# 01_COREBOARD.net
KiCad netlist of a schematic drawn in Altium Designer
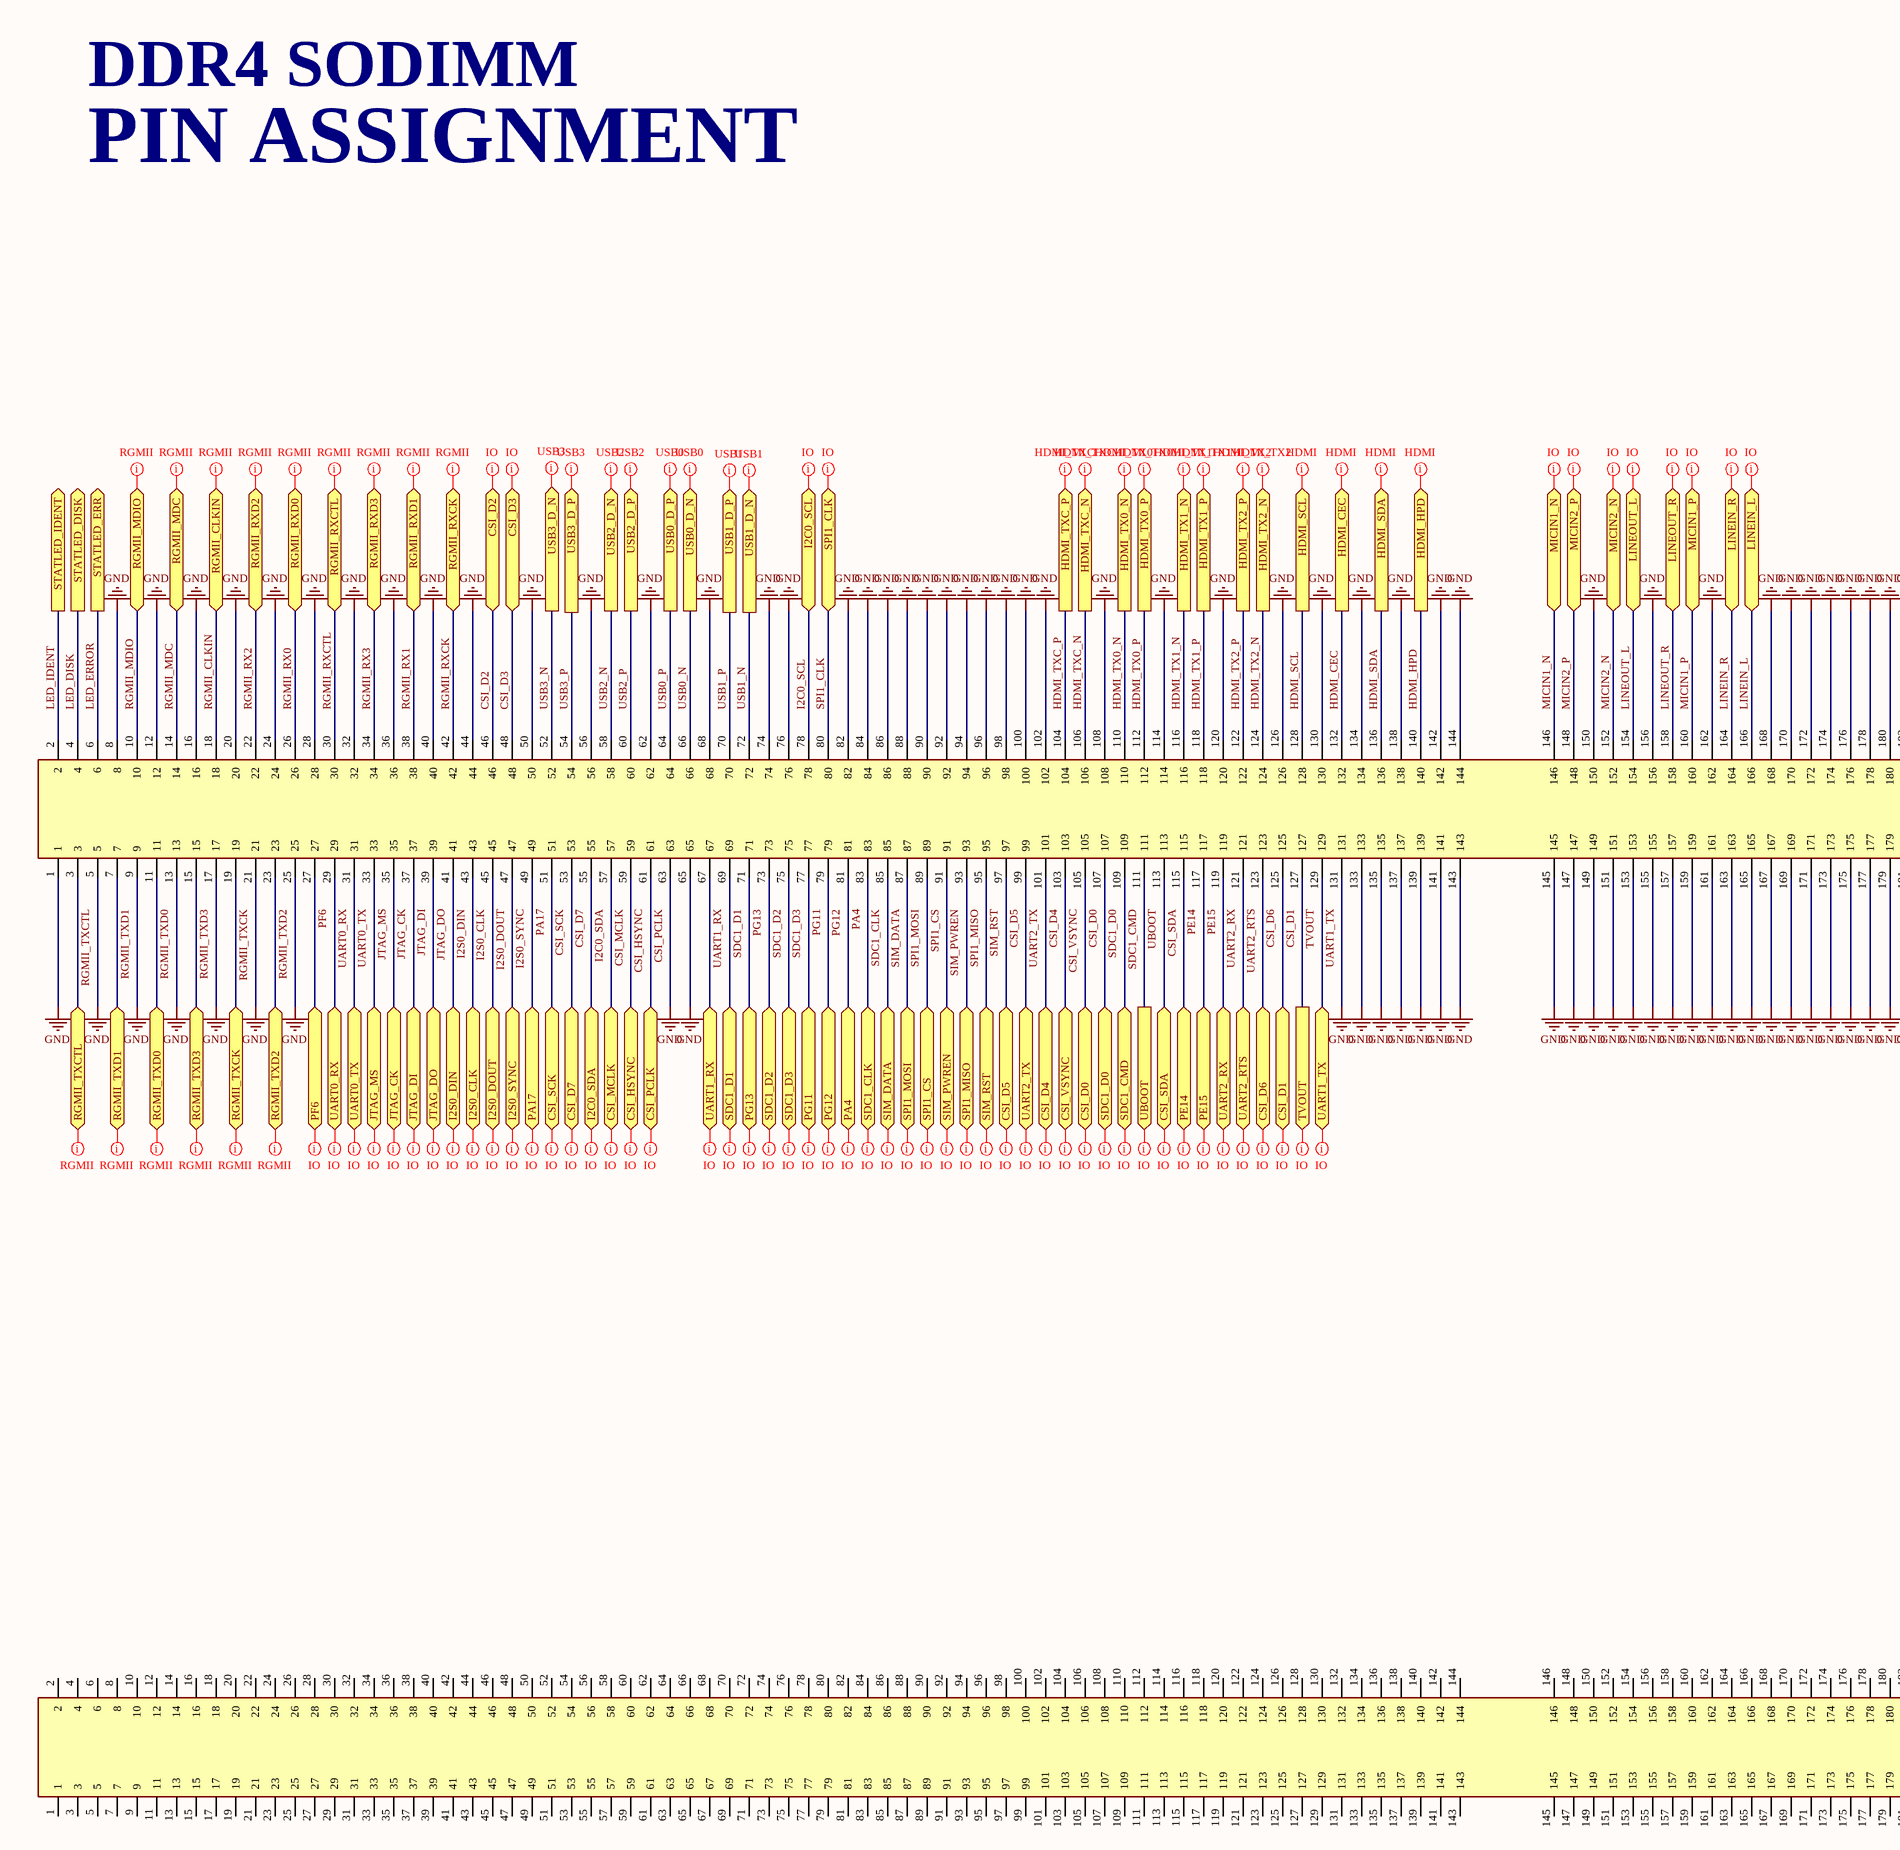
[diagram p0: 01_COREBOARD.SchDoc, left]
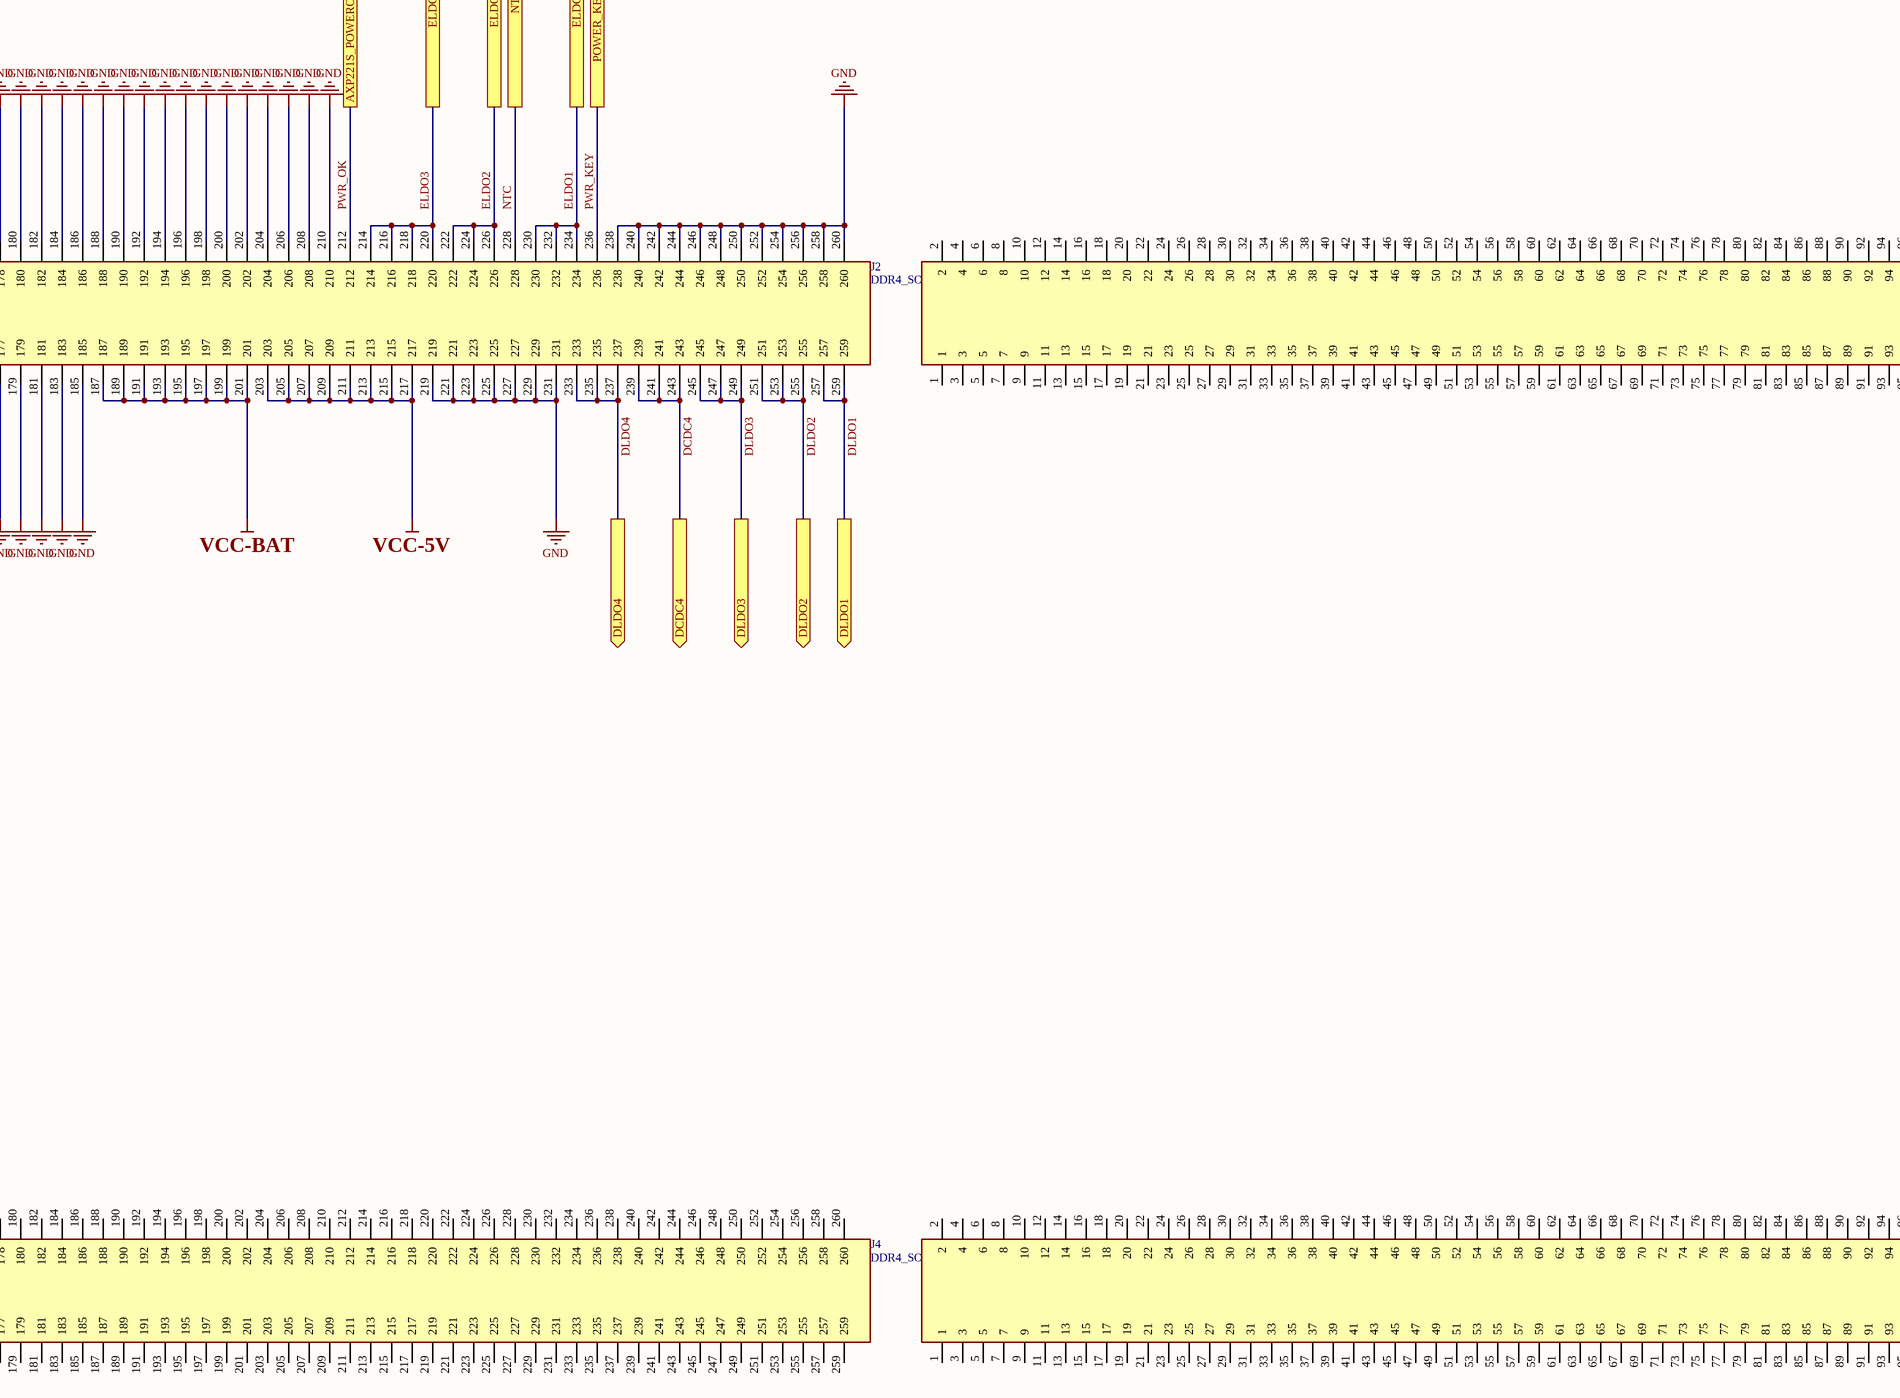
[diagram p1: 01_COREBOARD.SchDoc, middle]
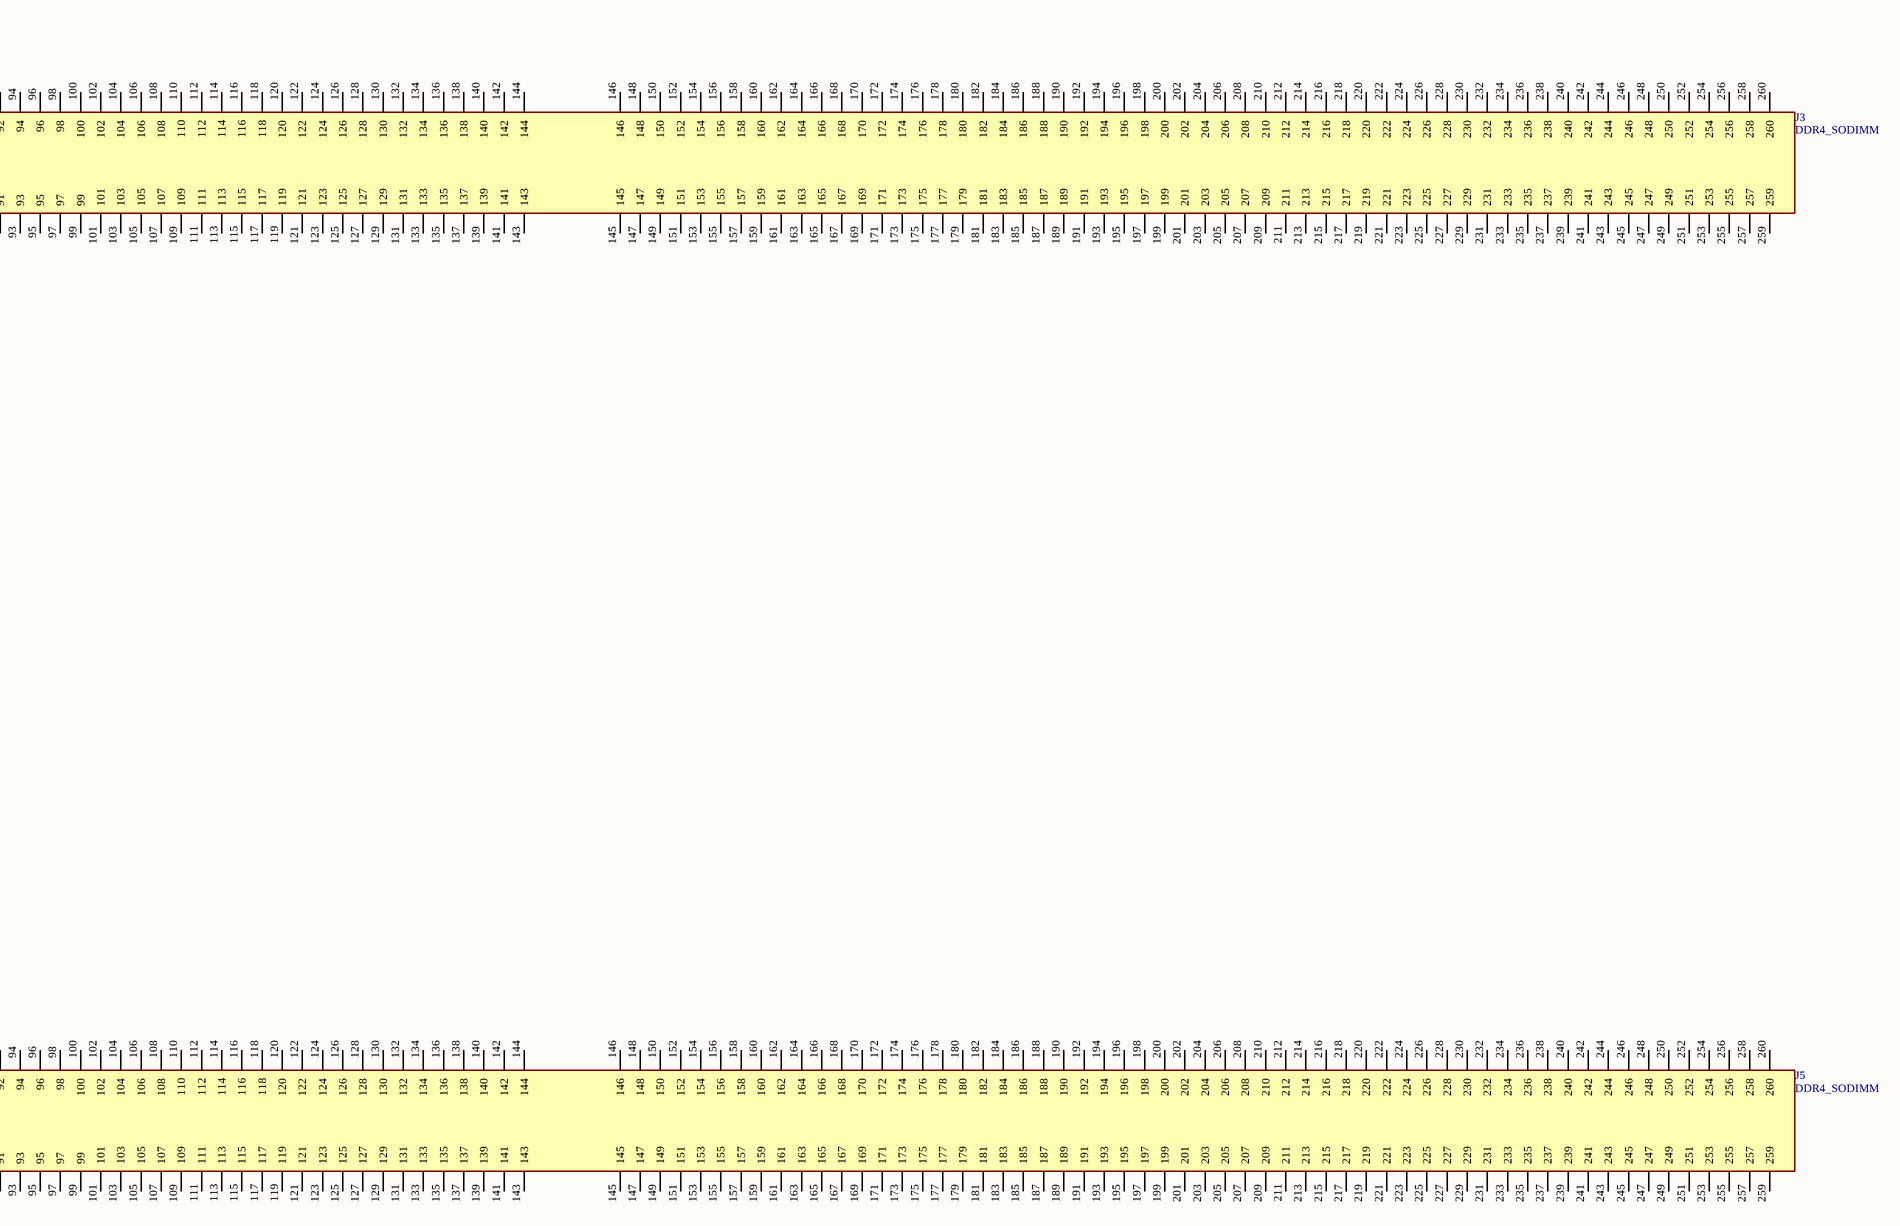
[diagram p2: 01_COREBOARD.SchDoc, right]

(export (version "E")
  (design (tool "Eeschema 10.0.6"))
  (components
    (comp (ref "J2")
      (value "DDR4_SODIMM")
      (footprint "DDR4_SODIMM")
      (libsource (lib "") (part "DDR4_SODIMM_1"))
    )
    (comp (ref "J3")
      (value "DDR4_SODIMM")
      (footprint "DDR4_SODIMM")
      (libsource (lib "MotherBoard") (part "DDR4_SODIMM"))
    )
    (comp (ref "J4")
      (value "DDR4_SODIMM")
      (footprint "DDR4_SODIMM")
      (libsource (lib "") (part "DDR4_SODIMM_1"))
    )
    (comp (ref "J5")
      (value "DDR4_SODIMM")
      (footprint "DDR4_SODIMM")
      (libsource (lib "MotherBoard") (part "DDR4_SODIMM"))
    )
  )
  (nets
    (net (code "1") (name "/CSI_D0") (class "Default")
      (node (ref "J2") (pin "105") (pinfunction "105_105") (pintype "passive"))
    )
    (net (code "2") (name "/CSI_D1") (class "Default")
      (node (ref "J2") (pin "125") (pinfunction "125_125") (pintype "passive"))
    )
    (net (code "3") (name "/CSI_D2") (class "Default")
      (node (ref "J2") (pin "46") (pinfunction "46_46") (pintype "passive"))
    )
    (net (code "4") (name "/CSI_D3") (class "Default")
      (node (ref "J2") (pin "48") (pinfunction "48_48") (pintype "passive"))
    )
    (net (code "5") (name "/CSI_D4") (class "Default")
      (node (ref "J2") (pin "101") (pinfunction "101_101") (pintype "passive"))
    )
    (net (code "6") (name "/CSI_D5") (class "Default")
      (node (ref "J2") (pin "97") (pinfunction "97_97") (pintype "passive"))
    )
    (net (code "7") (name "/CSI_D6") (class "Default")
      (node (ref "J2") (pin "123") (pinfunction "123_123") (pintype "passive"))
    )
    (net (code "8") (name "/CSI_D7") (class "Default")
      (node (ref "J2") (pin "53") (pinfunction "53_53") (pintype "passive"))
    )
    (net (code "9") (name "/CSI_HSYNC") (class "Default")
      (node (ref "J2") (pin "59") (pinfunction "59_59") (pintype "passive"))
    )
    (net (code "10") (name "/CSI_MCLK") (class "Default")
      (node (ref "J2") (pin "57") (pinfunction "57_57") (pintype "passive"))
    )
    (net (code "11") (name "/CSI_PCLK") (class "Default")
      (node (ref "J2") (pin "61") (pinfunction "61_61") (pintype "passive"))
    )
    (net (code "12") (name "/CSI_SCK") (class "Default")
      (node (ref "J2") (pin "51") (pinfunction "51_51") (pintype "passive"))
    )
    (net (code "13") (name "/CSI_SDA") (class "Default")
      (node (ref "J2") (pin "113") (pinfunction "113_113") (pintype "passive"))
    )
    (net (code "14") (name "/CSI_VSYNC") (class "Default")
      (node (ref "J2") (pin "103") (pinfunction "103_103") (pintype "passive"))
    )
    (net (code "15") (name "/DCDC4") (class "Default")
      (node (ref "J2") (pin "239") (pinfunction "239_239") (pintype "passive"))
      (node (ref "J2") (pin "241") (pinfunction "241_241") (pintype "passive"))
      (node (ref "J2") (pin "243") (pinfunction "243_243") (pintype "passive"))
    )
    (net (code "16") (name "/DLDO1") (class "Default")
      (node (ref "J2") (pin "257") (pinfunction "257_257") (pintype "passive"))
      (node (ref "J2") (pin "259") (pinfunction "259_259") (pintype "passive"))
    )
    (net (code "17") (name "/DLDO2") (class "Default")
      (node (ref "J2") (pin "251") (pinfunction "251_251") (pintype "passive"))
      (node (ref "J2") (pin "253") (pinfunction "253_253") (pintype "passive"))
      (node (ref "J2") (pin "255") (pinfunction "255_255") (pintype "passive"))
    )
    (net (code "18") (name "/DLDO3") (class "Default")
      (node (ref "J2") (pin "245") (pinfunction "245_245") (pintype "passive"))
      (node (ref "J2") (pin "247") (pinfunction "247_247") (pintype "passive"))
      (node (ref "J2") (pin "249") (pinfunction "249_249") (pintype "passive"))
    )
    (net (code "19") (name "/DLDO4") (class "Default")
      (node (ref "J2") (pin "233") (pinfunction "233_233") (pintype "passive"))
      (node (ref "J2") (pin "235") (pinfunction "235_235") (pintype "passive"))
      (node (ref "J2") (pin "237") (pinfunction "237_237") (pintype "passive"))
    )
    (net (code "20") (name "/ELDO1") (class "Default")
      (node (ref "J2") (pin "230") (pinfunction "230_230") (pintype "passive"))
      (node (ref "J2") (pin "232") (pinfunction "232_232") (pintype "passive"))
      (node (ref "J2") (pin "234") (pinfunction "234_234") (pintype "passive"))
    )
    (net (code "21") (name "/ELDO2") (class "Default")
      (node (ref "J2") (pin "222") (pinfunction "222_222") (pintype "passive"))
      (node (ref "J2") (pin "224") (pinfunction "224_224") (pintype "passive"))
      (node (ref "J2") (pin "226") (pinfunction "226_226") (pintype "passive"))
    )
    (net (code "22") (name "/ELDO3") (class "Default")
      (node (ref "J2") (pin "214") (pinfunction "214_214") (pintype "passive"))
      (node (ref "J2") (pin "216") (pinfunction "216_216") (pintype "passive"))
      (node (ref "J2") (pin "218") (pinfunction "218_218") (pintype "passive"))
      (node (ref "J2") (pin "220") (pinfunction "220_220") (pintype "passive"))
    )
    (net (code "23") (name "/HDMI_CEC") (class "Default")
      (node (ref "J2") (pin "132") (pinfunction "132_132") (pintype "passive"))
    )
    (net (code "24") (name "/HDMI_HPD") (class "Default")
      (node (ref "J2") (pin "140") (pinfunction "140_140") (pintype "passive"))
    )
    (net (code "25") (name "/HDMI_SCL") (class "Default")
      (node (ref "J2") (pin "128") (pinfunction "128_128") (pintype "passive"))
    )
    (net (code "26") (name "/HDMI_SDA") (class "Default")
      (node (ref "J2") (pin "136") (pinfunction "136_136") (pintype "passive"))
    )
    (net (code "27") (name "/HDMI_TX0_N") (class "Default")
      (node (ref "J2") (pin "110") (pinfunction "110_110") (pintype "passive"))
    )
    (net (code "28") (name "/HDMI_TX0_P") (class "Default")
      (node (ref "J2") (pin "112") (pinfunction "112_112") (pintype "passive"))
    )
    (net (code "29") (name "/HDMI_TX1_N") (class "Default")
      (node (ref "J2") (pin "116") (pinfunction "116_116") (pintype "passive"))
    )
    (net (code "30") (name "/HDMI_TX1_P") (class "Default")
      (node (ref "J2") (pin "118") (pinfunction "118_118") (pintype "passive"))
    )
    (net (code "31") (name "/HDMI_TX2_N") (class "Default")
      (node (ref "J2") (pin "124") (pinfunction "124_124") (pintype "passive"))
    )
    (net (code "32") (name "/HDMI_TX2_P") (class "Default")
      (node (ref "J2") (pin "122") (pinfunction "122_122") (pintype "passive"))
    )
    (net (code "33") (name "/HDMI_TXC_N") (class "Default")
      (node (ref "J2") (pin "106") (pinfunction "106_106") (pintype "passive"))
    )
    (net (code "34") (name "/HDMI_TXC_P") (class "Default")
      (node (ref "J2") (pin "104") (pinfunction "104_104") (pintype "passive"))
    )
    (net (code "35") (name "/I2C0_SCL") (class "Default")
      (node (ref "J2") (pin "78") (pinfunction "78_78") (pintype "passive"))
    )
    (net (code "36") (name "/I2C0_SDA") (class "Default")
      (node (ref "J2") (pin "55") (pinfunction "55_55") (pintype "passive"))
    )
    (net (code "37") (name "/I2S0_CLK") (class "Default")
      (node (ref "J2") (pin "43") (pinfunction "43_43") (pintype "passive"))
    )
    (net (code "38") (name "/I2S0_DIN") (class "Default")
      (node (ref "J2") (pin "41") (pinfunction "41_41") (pintype "passive"))
    )
    (net (code "39") (name "/I2S0_DOUT") (class "Default")
      (node (ref "J2") (pin "45") (pinfunction "45_45") (pintype "passive"))
    )
    (net (code "40") (name "/I2S0_SYNC") (class "Default")
      (node (ref "J2") (pin "47") (pinfunction "47_47") (pintype "passive"))
    )
    (net (code "41") (name "/JTAG_CK") (class "Default")
      (node (ref "J2") (pin "35") (pinfunction "35_35") (pintype "passive"))
    )
    (net (code "42") (name "/JTAG_DI") (class "Default")
      (node (ref "J2") (pin "37") (pinfunction "37_37") (pintype "passive"))
    )
    (net (code "43") (name "/JTAG_DO") (class "Default")
      (node (ref "J2") (pin "39") (pinfunction "39_39") (pintype "passive"))
    )
    (net (code "44") (name "/JTAG_MS") (class "Default")
      (node (ref "J2") (pin "33") (pinfunction "33_33") (pintype "passive"))
    )
    (net (code "45") (name "/LED_DISK") (class "Default")
      (node (ref "J2") (pin "4") (pinfunction "4_4") (pintype "passive"))
    )
    (net (code "46") (name "/LED_ERROR") (class "Default")
      (node (ref "J2") (pin "6") (pinfunction "6_6") (pintype "passive"))
    )
    (net (code "47") (name "/LED_IDENT") (class "Default")
      (node (ref "J2") (pin "2") (pinfunction "2_2") (pintype "passive"))
    )
    (net (code "48") (name "/LINEIN_L") (class "Default")
      (node (ref "J2") (pin "166") (pinfunction "166_166") (pintype "passive"))
    )
    (net (code "49") (name "/LINEIN_R") (class "Default")
      (node (ref "J2") (pin "164") (pinfunction "164_164") (pintype "passive"))
    )
    (net (code "50") (name "/LINEOUT_L") (class "Default")
      (node (ref "J2") (pin "154") (pinfunction "154_154") (pintype "passive"))
    )
    (net (code "51") (name "/LINEOUT_R") (class "Default")
      (node (ref "J2") (pin "158") (pinfunction "158_158") (pintype "passive"))
    )
    (net (code "52") (name "/MICIN1_N") (class "Default")
      (node (ref "J2") (pin "146") (pinfunction "146_146") (pintype "passive"))
    )
    (net (code "53") (name "/MICIN1_P") (class "Default")
      (node (ref "J2") (pin "160") (pinfunction "160_160") (pintype "passive"))
    )
    (net (code "54") (name "/MICIN2_N") (class "Default")
      (node (ref "J2") (pin "152") (pinfunction "152_152") (pintype "passive"))
    )
    (net (code "55") (name "/MICIN2_P") (class "Default")
      (node (ref "J2") (pin "148") (pinfunction "148_148") (pintype "passive"))
    )
    (net (code "56") (name "/NTC") (class "Default")
      (node (ref "J2") (pin "228") (pinfunction "228_228") (pintype "passive"))
    )
    (net (code "57") (name "/PA4") (class "Default")
      (node (ref "J2") (pin "81") (pinfunction "81_81") (pintype "passive"))
    )
    (net (code "58") (name "/PA17") (class "Default")
      (node (ref "J2") (pin "49") (pinfunction "49_49") (pintype "passive"))
    )
    (net (code "59") (name "/PE14") (class "Default")
      (node (ref "J2") (pin "115") (pinfunction "115_115") (pintype "passive"))
    )
    (net (code "60") (name "/PE15") (class "Default")
      (node (ref "J2") (pin "117") (pinfunction "117_117") (pintype "passive"))
    )
    (net (code "61") (name "/PF6") (class "Default")
      (node (ref "J2") (pin "27") (pinfunction "27_27") (pintype "passive"))
    )
    (net (code "62") (name "/PG11") (class "Default")
      (node (ref "J2") (pin "77") (pinfunction "77_77") (pintype "passive"))
    )
    (net (code "63") (name "/PG12") (class "Default")
      (node (ref "J2") (pin "79") (pinfunction "79_79") (pintype "passive"))
    )
    (net (code "64") (name "/PG13") (class "Default")
      (node (ref "J2") (pin "71") (pinfunction "71_71") (pintype "passive"))
    )
    (net (code "65") (name "/PWR_KEY") (class "Default")
      (node (ref "J2") (pin "236") (pinfunction "236_236") (pintype "passive"))
    )
    (net (code "66") (name "/PWR_OK") (class "Default")
      (node (ref "J2") (pin "212") (pinfunction "212_212") (pintype "passive"))
    )
    (net (code "67") (name "/RGMII_CLKIN") (class "Default")
      (node (ref "J2") (pin "18") (pinfunction "18_18") (pintype "passive"))
    )
    (net (code "68") (name "/RGMII_MDC") (class "Default")
      (node (ref "J2") (pin "14") (pinfunction "14_14") (pintype "passive"))
    )
    (net (code "69") (name "/RGMII_MDIO") (class "Default")
      (node (ref "J2") (pin "10") (pinfunction "10_10") (pintype "passive"))
    )
    (net (code "70") (name "/RGMII_RX0") (class "Default")
      (node (ref "J2") (pin "26") (pinfunction "26_26") (pintype "passive"))
    )
    (net (code "71") (name "/RGMII_RX1") (class "Default")
      (node (ref "J2") (pin "38") (pinfunction "38_38") (pintype "passive"))
    )
    (net (code "72") (name "/RGMII_RX2") (class "Default")
      (node (ref "J2") (pin "22") (pinfunction "22_22") (pintype "passive"))
    )
    (net (code "73") (name "/RGMII_RX3") (class "Default")
      (node (ref "J2") (pin "34") (pinfunction "34_34") (pintype "passive"))
    )
    (net (code "74") (name "/RGMII_RXCK") (class "Default")
      (node (ref "J2") (pin "42") (pinfunction "42_42") (pintype "passive"))
    )
    (net (code "75") (name "/RGMII_RXCTL") (class "Default")
      (node (ref "J2") (pin "30") (pinfunction "30_30") (pintype "passive"))
    )
    (net (code "76") (name "/RGMII_TXCK") (class "Default")
      (node (ref "J2") (pin "19") (pinfunction "19_19") (pintype "passive"))
    )
    (net (code "77") (name "/RGMII_TXCTL") (class "Default")
      (node (ref "J2") (pin "3") (pinfunction "3_3") (pintype "passive"))
    )
    (net (code "78") (name "/RGMII_TXD0") (class "Default")
      (node (ref "J2") (pin "11") (pinfunction "11_11") (pintype "passive"))
    )
    (net (code "79") (name "/RGMII_TXD1") (class "Default")
      (node (ref "J2") (pin "7") (pinfunction "7_7") (pintype "passive"))
    )
    (net (code "80") (name "/RGMII_TXD2") (class "Default")
      (node (ref "J2") (pin "23") (pinfunction "23_23") (pintype "passive"))
    )
    (net (code "81") (name "/RGMII_TXD3") (class "Default")
      (node (ref "J2") (pin "15") (pinfunction "15_15") (pintype "passive"))
    )
    (net (code "82") (name "/SDC1_CLK") (class "Default")
      (node (ref "J2") (pin "83") (pinfunction "83_83") (pintype "passive"))
    )
    (net (code "83") (name "/SDC1_CMD") (class "Default")
      (node (ref "J2") (pin "109") (pinfunction "109_109") (pintype "passive"))
    )
    (net (code "84") (name "/SDC1_D0") (class "Default")
      (node (ref "J2") (pin "107") (pinfunction "107_107") (pintype "passive"))
    )
    (net (code "85") (name "/SDC1_D1") (class "Default")
      (node (ref "J2") (pin "69") (pinfunction "69_69") (pintype "passive"))
    )
    (net (code "86") (name "/SDC1_D2") (class "Default")
      (node (ref "J2") (pin "73") (pinfunction "73_73") (pintype "passive"))
    )
    (net (code "87") (name "/SDC1_D3") (class "Default")
      (node (ref "J2") (pin "75") (pinfunction "75_75") (pintype "passive"))
    )
    (net (code "88") (name "/SIM_DATA") (class "Default")
      (node (ref "J2") (pin "85") (pinfunction "85_85") (pintype "passive"))
    )
    (net (code "89") (name "/SIM_PWREN") (class "Default")
      (node (ref "J2") (pin "91") (pinfunction "91_91") (pintype "passive"))
    )
    (net (code "90") (name "/SIM_RST") (class "Default")
      (node (ref "J2") (pin "95") (pinfunction "95_95") (pintype "passive"))
    )
    (net (code "91") (name "/SPI1_CLK") (class "Default")
      (node (ref "J2") (pin "80") (pinfunction "80_80") (pintype "passive"))
    )
    (net (code "92") (name "/SPI1_CS") (class "Default")
      (node (ref "J2") (pin "89") (pinfunction "89_89") (pintype "passive"))
    )
    (net (code "93") (name "/SPI1_MISO") (class "Default")
      (node (ref "J2") (pin "93") (pinfunction "93_93") (pintype "passive"))
    )
    (net (code "94") (name "/SPI1_MOSI") (class "Default")
      (node (ref "J2") (pin "87") (pinfunction "87_87") (pintype "passive"))
    )
    (net (code "95") (name "/TVOUT") (class "Default")
      (node (ref "J2") (pin "127") (pinfunction "127_127") (pintype "passive"))
    )
    (net (code "96") (name "/UART0_RX") (class "Default")
      (node (ref "J2") (pin "29") (pinfunction "29_29") (pintype "passive"))
    )
    (net (code "97") (name "/UART0_TX") (class "Default")
      (node (ref "J2") (pin "31") (pinfunction "31_31") (pintype "passive"))
    )
    (net (code "98") (name "/UART1_RX") (class "Default")
      (node (ref "J2") (pin "67") (pinfunction "67_67") (pintype "passive"))
    )
    (net (code "99") (name "/UART1_TX") (class "Default")
      (node (ref "J2") (pin "129") (pinfunction "129_129") (pintype "passive"))
    )
    (net (code "100") (name "/UART2_RTS") (class "Default")
      (node (ref "J2") (pin "121") (pinfunction "121_121") (pintype "passive"))
    )
    (net (code "101") (name "/UART2_RX") (class "Default")
      (node (ref "J2") (pin "119") (pinfunction "119_119") (pintype "passive"))
    )
    (net (code "102") (name "/UART2_TX") (class "Default")
      (node (ref "J2") (pin "99") (pinfunction "99_99") (pintype "passive"))
    )
    (net (code "103") (name "/UBOOT") (class "Default")
      (node (ref "J2") (pin "111") (pinfunction "111_111") (pintype "passive"))
    )
    (net (code "104") (name "/USB0_N") (class "Default")
      (node (ref "J2") (pin "66") (pinfunction "66_66") (pintype "passive"))
    )
    (net (code "105") (name "/USB0_P") (class "Default")
      (node (ref "J2") (pin "64") (pinfunction "64_64") (pintype "passive"))
    )
    (net (code "106") (name "/USB1_N") (class "Default")
      (node (ref "J2") (pin "72") (pinfunction "72_72") (pintype "passive"))
    )
    (net (code "107") (name "/USB1_P") (class "Default")
      (node (ref "J2") (pin "70") (pinfunction "70_70") (pintype "passive"))
    )
    (net (code "108") (name "/USB2_N") (class "Default")
      (node (ref "J2") (pin "58") (pinfunction "58_58") (pintype "passive"))
    )
    (net (code "109") (name "/USB2_P") (class "Default")
      (node (ref "J2") (pin "60") (pinfunction "60_60") (pintype "passive"))
    )
    (net (code "110") (name "/USB3_N") (class "Default")
      (node (ref "J2") (pin "52") (pinfunction "52_52") (pintype "passive"))
    )
    (net (code "111") (name "/USB3_P") (class "Default")
      (node (ref "J2") (pin "54") (pinfunction "54_54") (pintype "passive"))
    )
    (net (code "112") (name "GND") (class "Default")
      (node (ref "J2") (pin "1") (pinfunction "1_1") (pintype "passive"))
      (node (ref "J2") (pin "100") (pinfunction "100_100") (pintype "passive"))
      (node (ref "J2") (pin "102") (pinfunction "102_102") (pintype "passive"))
      (node (ref "J2") (pin "108") (pinfunction "108_108") (pintype "passive"))
      (node (ref "J2") (pin "114") (pinfunction "114_114") (pintype "passive"))
      (node (ref "J2") (pin "12") (pinfunction "12_12") (pintype "passive"))
      (node (ref "J2") (pin "120") (pinfunction "120_120") (pintype "passive"))
      (node (ref "J2") (pin "126") (pinfunction "126_126") (pintype "passive"))
      (node (ref "J2") (pin "13") (pinfunction "13_13") (pintype "passive"))
      (node (ref "J2") (pin "130") (pinfunction "130_130") (pintype "passive"))
      (node (ref "J2") (pin "131") (pinfunction "131_131") (pintype "passive"))
      (node (ref "J2") (pin "133") (pinfunction "133_133") (pintype "passive"))
      (node (ref "J2") (pin "134") (pinfunction "134_134") (pintype "passive"))
      (node (ref "J2") (pin "135") (pinfunction "135_135") (pintype "passive"))
      (node (ref "J2") (pin "137") (pinfunction "137_137") (pintype "passive"))
      (node (ref "J2") (pin "138") (pinfunction "138_138") (pintype "passive"))
      (node (ref "J2") (pin "139") (pinfunction "139_139") (pintype "passive"))
      (node (ref "J2") (pin "141") (pinfunction "141_141") (pintype "passive"))
      (node (ref "J2") (pin "142") (pinfunction "142_142") (pintype "passive"))
      (node (ref "J2") (pin "143") (pinfunction "143_143") (pintype "passive"))
      (node (ref "J2") (pin "144") (pinfunction "144_144") (pintype "passive"))
      (node (ref "J2") (pin "145") (pinfunction "145_145") (pintype "passive"))
      (node (ref "J2") (pin "147") (pinfunction "147_147") (pintype "passive"))
      (node (ref "J2") (pin "149") (pinfunction "149_149") (pintype "passive"))
      (node (ref "J2") (pin "150") (pinfunction "150_150") (pintype "passive"))
      (node (ref "J2") (pin "151") (pinfunction "151_151") (pintype "passive"))
      (node (ref "J2") (pin "153") (pinfunction "153_153") (pintype "passive"))
      (node (ref "J2") (pin "155") (pinfunction "155_155") (pintype "passive"))
      (node (ref "J2") (pin "156") (pinfunction "156_156") (pintype "passive"))
      (node (ref "J2") (pin "157") (pinfunction "157_157") (pintype "passive"))
      (node (ref "J2") (pin "159") (pinfunction "159_159") (pintype "passive"))
      (node (ref "J2") (pin "16") (pinfunction "16_16") (pintype "passive"))
      (node (ref "J2") (pin "161") (pinfunction "161_161") (pintype "passive"))
      (node (ref "J2") (pin "162") (pinfunction "162_162") (pintype "passive"))
      (node (ref "J2") (pin "163") (pinfunction "163_163") (pintype "passive"))
      (node (ref "J2") (pin "165") (pinfunction "165_165") (pintype "passive"))
      (node (ref "J2") (pin "167") (pinfunction "167_167") (pintype "passive"))
      (node (ref "J2") (pin "168") (pinfunction "168_168") (pintype "passive"))
      (node (ref "J2") (pin "169") (pinfunction "169_169") (pintype "passive"))
      (node (ref "J2") (pin "17") (pinfunction "17_17") (pintype "passive"))
      (node (ref "J2") (pin "170") (pinfunction "170_170") (pintype "passive"))
      (node (ref "J2") (pin "171") (pinfunction "171_171") (pintype "passive"))
      (node (ref "J2") (pin "172") (pinfunction "172_172") (pintype "passive"))
      (node (ref "J2") (pin "173") (pinfunction "173_173") (pintype "passive"))
      (node (ref "J2") (pin "174") (pinfunction "174_174") (pintype "passive"))
      (node (ref "J2") (pin "175") (pinfunction "175_175") (pintype "passive"))
      (node (ref "J2") (pin "176") (pinfunction "176_176") (pintype "passive"))
      (node (ref "J2") (pin "177") (pinfunction "177_177") (pintype "passive"))
      (node (ref "J2") (pin "178") (pinfunction "178_178") (pintype "passive"))
      (node (ref "J2") (pin "179") (pinfunction "179_179") (pintype "passive"))
      (node (ref "J2") (pin "180") (pinfunction "180_180") (pintype "passive"))
      (node (ref "J2") (pin "181") (pinfunction "181_181") (pintype "passive"))
      (node (ref "J2") (pin "182") (pinfunction "182_182") (pintype "passive"))
      (node (ref "J2") (pin "183") (pinfunction "183_183") (pintype "passive"))
      (node (ref "J2") (pin "184") (pinfunction "184_184") (pintype "passive"))
      (node (ref "J2") (pin "185") (pinfunction "185_185") (pintype "passive"))
      (node (ref "J2") (pin "186") (pinfunction "186_186") (pintype "passive"))
      (node (ref "J2") (pin "188") (pinfunction "188_188") (pintype "passive"))
      (node (ref "J2") (pin "190") (pinfunction "190_190") (pintype "passive"))
      (node (ref "J2") (pin "192") (pinfunction "192_192") (pintype "passive"))
      (node (ref "J2") (pin "194") (pinfunction "194_194") (pintype "passive"))
      (node (ref "J2") (pin "196") (pinfunction "196_196") (pintype "passive"))
      (node (ref "J2") (pin "198") (pinfunction "198_198") (pintype "passive"))
      (node (ref "J2") (pin "20") (pinfunction "20_20") (pintype "passive"))
      (node (ref "J2") (pin "200") (pinfunction "200_200") (pintype "passive"))
      (node (ref "J2") (pin "202") (pinfunction "202_202") (pintype "passive"))
      (node (ref "J2") (pin "204") (pinfunction "204_204") (pintype "passive"))
      (node (ref "J2") (pin "206") (pinfunction "206_206") (pintype "passive"))
      (node (ref "J2") (pin "208") (pinfunction "208_208") (pintype "passive"))
      (node (ref "J2") (pin "21") (pinfunction "21_21") (pintype "passive"))
      (node (ref "J2") (pin "210") (pinfunction "210_210") (pintype "passive"))
      (node (ref "J2") (pin "219") (pinfunction "219_219") (pintype "passive"))
      (node (ref "J2") (pin "221") (pinfunction "221_221") (pintype "passive"))
      (node (ref "J2") (pin "223") (pinfunction "223_223") (pintype "passive"))
      (node (ref "J2") (pin "225") (pinfunction "225_225") (pintype "passive"))
      (node (ref "J2") (pin "227") (pinfunction "227_227") (pintype "passive"))
      (node (ref "J2") (pin "229") (pinfunction "229_229") (pintype "passive"))
      (node (ref "J2") (pin "231") (pinfunction "231_231") (pintype "passive"))
      (node (ref "J2") (pin "238") (pinfunction "238_238") (pintype "passive"))
      (node (ref "J2") (pin "24") (pinfunction "24_24") (pintype "passive"))
      (node (ref "J2") (pin "240") (pinfunction "240_240") (pintype "passive"))
      (node (ref "J2") (pin "242") (pinfunction "242_242") (pintype "passive"))
      (node (ref "J2") (pin "244") (pinfunction "244_244") (pintype "passive"))
      (node (ref "J2") (pin "246") (pinfunction "246_246") (pintype "passive"))
      (node (ref "J2") (pin "248") (pinfunction "248_248") (pintype "passive"))
      (node (ref "J2") (pin "25") (pinfunction "25_25") (pintype "passive"))
      (node (ref "J2") (pin "250") (pinfunction "250_250") (pintype "passive"))
      (node (ref "J2") (pin "252") (pinfunction "252_252") (pintype "passive"))
      (node (ref "J2") (pin "254") (pinfunction "254_254") (pintype "passive"))
      (node (ref "J2") (pin "256") (pinfunction "256_256") (pintype "passive"))
      (node (ref "J2") (pin "258") (pinfunction "258_258") (pintype "passive"))
      (node (ref "J2") (pin "260") (pinfunction "260_260") (pintype "passive"))
      (node (ref "J2") (pin "28") (pinfunction "28_28") (pintype "passive"))
      (node (ref "J2") (pin "32") (pinfunction "32_32") (pintype "passive"))
      (node (ref "J2") (pin "36") (pinfunction "36_36") (pintype "passive"))
      (node (ref "J2") (pin "40") (pinfunction "40_40") (pintype "passive"))
      (node (ref "J2") (pin "44") (pinfunction "44_44") (pintype "passive"))
      (node (ref "J2") (pin "5") (pinfunction "5_5") (pintype "passive"))
      (node (ref "J2") (pin "50") (pinfunction "50_50") (pintype "passive"))
      (node (ref "J2") (pin "56") (pinfunction "56_56") (pintype "passive"))
      (node (ref "J2") (pin "62") (pinfunction "62_62") (pintype "passive"))
      (node (ref "J2") (pin "63") (pinfunction "63_63") (pintype "passive"))
      (node (ref "J2") (pin "65") (pinfunction "65_65") (pintype "passive"))
      (node (ref "J2") (pin "68") (pinfunction "68_68") (pintype "passive"))
      (node (ref "J2") (pin "74") (pinfunction "74_74") (pintype "passive"))
      (node (ref "J2") (pin "76") (pinfunction "76_76") (pintype "passive"))
      (node (ref "J2") (pin "8") (pinfunction "8_8") (pintype "passive"))
      (node (ref "J2") (pin "82") (pinfunction "82_82") (pintype "passive"))
      (node (ref "J2") (pin "84") (pinfunction "84_84") (pintype "passive"))
      (node (ref "J2") (pin "86") (pinfunction "86_86") (pintype "passive"))
      (node (ref "J2") (pin "88") (pinfunction "88_88") (pintype "passive"))
      (node (ref "J2") (pin "9") (pinfunction "9_9") (pintype "passive"))
      (node (ref "J2") (pin "90") (pinfunction "90_90") (pintype "passive"))
      (node (ref "J2") (pin "92") (pinfunction "92_92") (pintype "passive"))
      (node (ref "J2") (pin "94") (pinfunction "94_94") (pintype "passive"))
      (node (ref "J2") (pin "96") (pinfunction "96_96") (pintype "passive"))
      (node (ref "J2") (pin "98") (pinfunction "98_98") (pintype "passive"))
    )
    (net (code "113") (name "VCC-5V") (class "Default")
      (node (ref "J2") (pin "203") (pinfunction "203_203") (pintype "passive"))
      (node (ref "J2") (pin "205") (pinfunction "205_205") (pintype "passive"))
      (node (ref "J2") (pin "207") (pinfunction "207_207") (pintype "passive"))
      (node (ref "J2") (pin "209") (pinfunction "209_209") (pintype "passive"))
      (node (ref "J2") (pin "211") (pinfunction "211_211") (pintype "passive"))
      (node (ref "J2") (pin "213") (pinfunction "213_213") (pintype "passive"))
      (node (ref "J2") (pin "215") (pinfunction "215_215") (pintype "passive"))
      (node (ref "J2") (pin "217") (pinfunction "217_217") (pintype "passive"))
    )
    (net (code "114") (name "VCC-BAT") (class "Default")
      (node (ref "J2") (pin "187") (pinfunction "187_187") (pintype "passive"))
      (node (ref "J2") (pin "189") (pinfunction "189_189") (pintype "passive"))
      (node (ref "J2") (pin "191") (pinfunction "191_191") (pintype "passive"))
      (node (ref "J2") (pin "193") (pinfunction "193_193") (pintype "passive"))
      (node (ref "J2") (pin "195") (pinfunction "195_195") (pintype "passive"))
      (node (ref "J2") (pin "197") (pinfunction "197_197") (pintype "passive"))
      (node (ref "J2") (pin "199") (pinfunction "199_199") (pintype "passive"))
      (node (ref "J2") (pin "201") (pinfunction "201_201") (pintype "passive"))
    )
    (net (code "115") (name "unconnected-(J3-Pad1)") (class "Default")
      (node (ref "J3") (pin "1") (pinfunction "1_1") (pintype "passive"))
    )
    (net (code "116") (name "unconnected-(J3-Pad2)") (class "Default")
      (node (ref "J3") (pin "2") (pinfunction "2_2") (pintype "passive"))
    )
    (net (code "117") (name "unconnected-(J3-Pad3)") (class "Default")
      (node (ref "J3") (pin "3") (pinfunction "3_3") (pintype "passive"))
    )
    (net (code "118") (name "unconnected-(J3-Pad4)") (class "Default")
      (node (ref "J3") (pin "4") (pinfunction "4_4") (pintype "passive"))
    )
    (net (code "119") (name "unconnected-(J3-Pad5)") (class "Default")
      (node (ref "J3") (pin "5") (pinfunction "5_5") (pintype "passive"))
    )
    (net (code "120") (name "unconnected-(J3-Pad6)") (class "Default")
      (node (ref "J3") (pin "6") (pinfunction "6_6") (pintype "passive"))
    )
    (net (code "121") (name "unconnected-(J3-Pad7)") (class "Default")
      (node (ref "J3") (pin "7") (pinfunction "7_7") (pintype "passive"))
    )
    (net (code "122") (name "unconnected-(J3-Pad8)") (class "Default")
      (node (ref "J3") (pin "8") (pinfunction "8_8") (pintype "passive"))
    )
    (net (code "123") (name "unconnected-(J3-Pad9)") (class "Default")
      (node (ref "J3") (pin "9") (pinfunction "9_9") (pintype "passive"))
    )
    (net (code "124") (name "unconnected-(J3-Pad10)") (class "Default")
      (node (ref "J3") (pin "10") (pinfunction "10_10") (pintype "passive"))
    )
    (net (code "125") (name "unconnected-(J3-Pad11)") (class "Default")
      (node (ref "J3") (pin "11") (pinfunction "11_11") (pintype "passive"))
    )
    (net (code "126") (name "unconnected-(J3-Pad12)") (class "Default")
      (node (ref "J3") (pin "12") (pinfunction "12_12") (pintype "passive"))
    )
    (net (code "127") (name "unconnected-(J3-Pad13)") (class "Default")
      (node (ref "J3") (pin "13") (pinfunction "13_13") (pintype "passive"))
    )
    (net (code "128") (name "unconnected-(J3-Pad14)") (class "Default")
      (node (ref "J3") (pin "14") (pinfunction "14_14") (pintype "passive"))
    )
    (net (code "129") (name "unconnected-(J3-Pad15)") (class "Default")
      (node (ref "J3") (pin "15") (pinfunction "15_15") (pintype "passive"))
    )
    (net (code "130") (name "unconnected-(J3-Pad16)") (class "Default")
      (node (ref "J3") (pin "16") (pinfunction "16_16") (pintype "passive"))
    )
    (net (code "131") (name "unconnected-(J3-Pad17)") (class "Default")
      (node (ref "J3") (pin "17") (pinfunction "17_17") (pintype "passive"))
    )
    (net (code "132") (name "unconnected-(J3-Pad18)") (class "Default")
      (node (ref "J3") (pin "18") (pinfunction "18_18") (pintype "passive"))
    )
    (net (code "133") (name "unconnected-(J3-Pad19)") (class "Default")
      (node (ref "J3") (pin "19") (pinfunction "19_19") (pintype "passive"))
    )
    (net (code "134") (name "unconnected-(J3-Pad20)") (class "Default")
      (node (ref "J3") (pin "20") (pinfunction "20_20") (pintype "passive"))
    )
    (net (code "135") (name "unconnected-(J3-Pad21)") (class "Default")
      (node (ref "J3") (pin "21") (pinfunction "21_21") (pintype "passive"))
    )
    (net (code "136") (name "unconnected-(J3-Pad22)") (class "Default")
      (node (ref "J3") (pin "22") (pinfunction "22_22") (pintype "passive"))
    )
    (net (code "137") (name "unconnected-(J3-Pad23)") (class "Default")
      (node (ref "J3") (pin "23") (pinfunction "23_23") (pintype "passive"))
    )
    (net (code "138") (name "unconnected-(J3-Pad24)") (class "Default")
      (node (ref "J3") (pin "24") (pinfunction "24_24") (pintype "passive"))
    )
    (net (code "139") (name "unconnected-(J3-Pad25)") (class "Default")
      (node (ref "J3") (pin "25") (pinfunction "25_25") (pintype "passive"))
    )
    (net (code "140") (name "unconnected-(J3-Pad26)") (class "Default")
      (node (ref "J3") (pin "26") (pinfunction "26_26") (pintype "passive"))
    )
    (net (code "141") (name "unconnected-(J3-Pad27)") (class "Default")
      (node (ref "J3") (pin "27") (pinfunction "27_27") (pintype "passive"))
    )
    (net (code "142") (name "unconnected-(J3-Pad28)") (class "Default")
      (node (ref "J3") (pin "28") (pinfunction "28_28") (pintype "passive"))
    )
    (net (code "143") (name "unconnected-(J3-Pad29)") (class "Default")
      (node (ref "J3") (pin "29") (pinfunction "29_29") (pintype "passive"))
    )
    (net (code "144") (name "unconnected-(J3-Pad30)") (class "Default")
      (node (ref "J3") (pin "30") (pinfunction "30_30") (pintype "passive"))
    )
    (net (code "145") (name "unconnected-(J3-Pad31)") (class "Default")
      (node (ref "J3") (pin "31") (pinfunction "31_31") (pintype "passive"))
    )
    (net (code "146") (name "unconnected-(J3-Pad32)") (class "Default")
      (node (ref "J3") (pin "32") (pinfunction "32_32") (pintype "passive"))
    )
    (net (code "147") (name "unconnected-(J3-Pad33)") (class "Default")
      (node (ref "J3") (pin "33") (pinfunction "33_33") (pintype "passive"))
    )
    (net (code "148") (name "unconnected-(J3-Pad34)") (class "Default")
      (node (ref "J3") (pin "34") (pinfunction "34_34") (pintype "passive"))
    )
    (net (code "149") (name "unconnected-(J3-Pad35)") (class "Default")
      (node (ref "J3") (pin "35") (pinfunction "35_35") (pintype "passive"))
    )
    (net (code "150") (name "unconnected-(J3-Pad36)") (class "Default")
      (node (ref "J3") (pin "36") (pinfunction "36_36") (pintype "passive"))
    )
    (net (code "151") (name "unconnected-(J3-Pad37)") (class "Default")
      (node (ref "J3") (pin "37") (pinfunction "37_37") (pintype "passive"))
    )
    (net (code "152") (name "unconnected-(J3-Pad38)") (class "Default")
      (node (ref "J3") (pin "38") (pinfunction "38_38") (pintype "passive"))
    )
    (net (code "153") (name "unconnected-(J3-Pad39)") (class "Default")
      (node (ref "J3") (pin "39") (pinfunction "39_39") (pintype "passive"))
    )
    (net (code "154") (name "unconnected-(J3-Pad40)") (class "Default")
      (node (ref "J3") (pin "40") (pinfunction "40_40") (pintype "passive"))
    )
    (net (code "155") (name "unconnected-(J3-Pad41)") (class "Default")
      (node (ref "J3") (pin "41") (pinfunction "41_41") (pintype "passive"))
    )
    (net (code "156") (name "unconnected-(J3-Pad42)") (class "Default")
      (node (ref "J3") (pin "42") (pinfunction "42_42") (pintype "passive"))
    )
    (net (code "157") (name "unconnected-(J3-Pad43)") (class "Default")
      (node (ref "J3") (pin "43") (pinfunction "43_43") (pintype "passive"))
    )
    (net (code "158") (name "unconnected-(J3-Pad44)") (class "Default")
      (node (ref "J3") (pin "44") (pinfunction "44_44") (pintype "passive"))
    )
    (net (code "159") (name "unconnected-(J3-Pad45)") (class "Default")
      (node (ref "J3") (pin "45") (pinfunction "45_45") (pintype "passive"))
    )
    (net (code "160") (name "unconnected-(J3-Pad46)") (class "Default")
      (node (ref "J3") (pin "46") (pinfunction "46_46") (pintype "passive"))
    )
    (net (code "161") (name "unconnected-(J3-Pad47)") (class "Default")
      (node (ref "J3") (pin "47") (pinfunction "47_47") (pintype "passive"))
    )
    (net (code "162") (name "unconnected-(J3-Pad48)") (class "Default")
      (node (ref "J3") (pin "48") (pinfunction "48_48") (pintype "passive"))
    )
    (net (code "163") (name "unconnected-(J3-Pad49)") (class "Default")
      (node (ref "J3") (pin "49") (pinfunction "49_49") (pintype "passive"))
    )
    (net (code "164") (name "unconnected-(J3-Pad50)") (class "Default")
      (node (ref "J3") (pin "50") (pinfunction "50_50") (pintype "passive"))
    )
    (net (code "165") (name "unconnected-(J3-Pad51)") (class "Default")
      (node (ref "J3") (pin "51") (pinfunction "51_51") (pintype "passive"))
    )
    (net (code "166") (name "unconnected-(J3-Pad52)") (class "Default")
      (node (ref "J3") (pin "52") (pinfunction "52_52") (pintype "passive"))
    )
    (net (code "167") (name "unconnected-(J3-Pad53)") (class "Default")
      (node (ref "J3") (pin "53") (pinfunction "53_53") (pintype "passive"))
    )
    (net (code "168") (name "unconnected-(J3-Pad54)") (class "Default")
      (node (ref "J3") (pin "54") (pinfunction "54_54") (pintype "passive"))
    )
    (net (code "169") (name "unconnected-(J3-Pad55)") (class "Default")
      (node (ref "J3") (pin "55") (pinfunction "55_55") (pintype "passive"))
    )
    (net (code "170") (name "unconnected-(J3-Pad56)") (class "Default")
      (node (ref "J3") (pin "56") (pinfunction "56_56") (pintype "passive"))
    )
    (net (code "171") (name "unconnected-(J3-Pad57)") (class "Default")
      (node (ref "J3") (pin "57") (pinfunction "57_57") (pintype "passive"))
    )
    (net (code "172") (name "unconnected-(J3-Pad58)") (class "Default")
      (node (ref "J3") (pin "58") (pinfunction "58_58") (pintype "passive"))
    )
    (net (code "173") (name "unconnected-(J3-Pad59)") (class "Default")
      (node (ref "J3") (pin "59") (pinfunction "59_59") (pintype "passive"))
    )
    (net (code "174") (name "unconnected-(J3-Pad60)") (class "Default")
      (node (ref "J3") (pin "60") (pinfunction "60_60") (pintype "passive"))
    )
    (net (code "175") (name "unconnected-(J3-Pad61)") (class "Default")
      (node (ref "J3") (pin "61") (pinfunction "61_61") (pintype "passive"))
    )
    (net (code "176") (name "unconnected-(J3-Pad62)") (class "Default")
      (node (ref "J3") (pin "62") (pinfunction "62_62") (pintype "passive"))
    )
    (net (code "177") (name "unconnected-(J3-Pad63)") (class "Default")
      (node (ref "J3") (pin "63") (pinfunction "63_63") (pintype "passive"))
    )
    (net (code "178") (name "unconnected-(J3-Pad64)") (class "Default")
      (node (ref "J3") (pin "64") (pinfunction "64_64") (pintype "passive"))
    )
    (net (code "179") (name "unconnected-(J3-Pad65)") (class "Default")
      (node (ref "J3") (pin "65") (pinfunction "65_65") (pintype "passive"))
    )
    (net (code "180") (name "unconnected-(J3-Pad66)") (class "Default")
      (node (ref "J3") (pin "66") (pinfunction "66_66") (pintype "passive"))
    )
    (net (code "181") (name "unconnected-(J3-Pad67)") (class "Default")
      (node (ref "J3") (pin "67") (pinfunction "67_67") (pintype "passive"))
    )
    (net (code "182") (name "unconnected-(J3-Pad68)") (class "Default")
      (node (ref "J3") (pin "68") (pinfunction "68_68") (pintype "passive"))
    )
    (net (code "183") (name "unconnected-(J3-Pad69)") (class "Default")
      (node (ref "J3") (pin "69") (pinfunction "69_69") (pintype "passive"))
    )
    (net (code "184") (name "unconnected-(J3-Pad70)") (class "Default")
      (node (ref "J3") (pin "70") (pinfunction "70_70") (pintype "passive"))
    )
    (net (code "185") (name "unconnected-(J3-Pad71)") (class "Default")
      (node (ref "J3") (pin "71") (pinfunction "71_71") (pintype "passive"))
    )
    (net (code "186") (name "unconnected-(J3-Pad72)") (class "Default")
      (node (ref "J3") (pin "72") (pinfunction "72_72") (pintype "passive"))
    )
    (net (code "187") (name "unconnected-(J3-Pad73)") (class "Default")
      (node (ref "J3") (pin "73") (pinfunction "73_73") (pintype "passive"))
    )
    (net (code "188") (name "unconnected-(J3-Pad74)") (class "Default")
      (node (ref "J3") (pin "74") (pinfunction "74_74") (pintype "passive"))
    )
    (net (code "189") (name "unconnected-(J3-Pad75)") (class "Default")
      (node (ref "J3") (pin "75") (pinfunction "75_75") (pintype "passive"))
    )
    (net (code "190") (name "unconnected-(J3-Pad76)") (class "Default")
      (node (ref "J3") (pin "76") (pinfunction "76_76") (pintype "passive"))
    )
    (net (code "191") (name "unconnected-(J3-Pad77)") (class "Default")
      (node (ref "J3") (pin "77") (pinfunction "77_77") (pintype "passive"))
    )
    (net (code "192") (name "unconnected-(J3-Pad78)") (class "Default")
      (node (ref "J3") (pin "78") (pinfunction "78_78") (pintype "passive"))
    )
    (net (code "193") (name "unconnected-(J3-Pad79)") (class "Default")
      (node (ref "J3") (pin "79") (pinfunction "79_79") (pintype "passive"))
    )
    (net (code "194") (name "unconnected-(J3-Pad80)") (class "Default")
      (node (ref "J3") (pin "80") (pinfunction "80_80") (pintype "passive"))
    )
    (net (code "195") (name "unconnected-(J3-Pad81)") (class "Default")
      (node (ref "J3") (pin "81") (pinfunction "81_81") (pintype "passive"))
    )
    (net (code "196") (name "unconnected-(J3-Pad82)") (class "Default")
      (node (ref "J3") (pin "82") (pinfunction "82_82") (pintype "passive"))
    )
    (net (code "197") (name "unconnected-(J3-Pad83)") (class "Default")
      (node (ref "J3") (pin "83") (pinfunction "83_83") (pintype "passive"))
    )
    (net (code "198") (name "unconnected-(J3-Pad84)") (class "Default")
      (node (ref "J3") (pin "84") (pinfunction "84_84") (pintype "passive"))
    )
    (net (code "199") (name "unconnected-(J3-Pad85)") (class "Default")
      (node (ref "J3") (pin "85") (pinfunction "85_85") (pintype "passive"))
    )
    (net (code "200") (name "unconnected-(J3-Pad86)") (class "Default")
      (node (ref "J3") (pin "86") (pinfunction "86_86") (pintype "passive"))
    )
    (net (code "201") (name "unconnected-(J3-Pad87)") (class "Default")
      (node (ref "J3") (pin "87") (pinfunction "87_87") (pintype "passive"))
    )
    (net (code "202") (name "unconnected-(J3-Pad88)") (class "Default")
      (node (ref "J3") (pin "88") (pinfunction "88_88") (pintype "passive"))
    )
    (net (code "203") (name "unconnected-(J3-Pad89)") (class "Default")
      (node (ref "J3") (pin "89") (pinfunction "89_89") (pintype "passive"))
    )
    (net (code "204") (name "unconnected-(J3-Pad90)") (class "Default")
      (node (ref "J3") (pin "90") (pinfunction "90_90") (pintype "passive"))
    )
    (net (code "205") (name "unconnected-(J3-Pad91)") (class "Default")
      (node (ref "J3") (pin "91") (pinfunction "91_91") (pintype "passive"))
    )
    (net (code "206") (name "unconnected-(J3-Pad92)") (class "Default")
      (node (ref "J3") (pin "92") (pinfunction "92_92") (pintype "passive"))
    )
    (net (code "207") (name "unconnected-(J3-Pad93)") (class "Default")
      (node (ref "J3") (pin "93") (pinfunction "93_93") (pintype "passive"))
    )
    (net (code "208") (name "unconnected-(J3-Pad94)") (class "Default")
      (node (ref "J3") (pin "94") (pinfunction "94_94") (pintype "passive"))
    )
    (net (code "209") (name "unconnected-(J3-Pad95)") (class "Default")
      (node (ref "J3") (pin "95") (pinfunction "95_95") (pintype "passive"))
    )
    (net (code "210") (name "unconnected-(J3-Pad96)") (class "Default")
      (node (ref "J3") (pin "96") (pinfunction "96_96") (pintype "passive"))
    )
    (net (code "211") (name "unconnected-(J3-Pad97)") (class "Default")
      (node (ref "J3") (pin "97") (pinfunction "97_97") (pintype "passive"))
    )
    (net (code "212") (name "unconnected-(J3-Pad98)") (class "Default")
      (node (ref "J3") (pin "98") (pinfunction "98_98") (pintype "passive"))
    )
    (net (code "213") (name "unconnected-(J3-Pad99)") (class "Default")
      (node (ref "J3") (pin "99") (pinfunction "99_99") (pintype "passive"))
    )
    (net (code "214") (name "unconnected-(J3-Pad100)") (class "Default")
      (node (ref "J3") (pin "100") (pinfunction "100_100") (pintype "passive"))
    )
    (net (code "215") (name "unconnected-(J3-Pad101)") (class "Default")
      (node (ref "J3") (pin "101") (pinfunction "101_101") (pintype "passive"))
    )
    (net (code "216") (name "unconnected-(J3-Pad102)") (class "Default")
      (node (ref "J3") (pin "102") (pinfunction "102_102") (pintype "passive"))
    )
    (net (code "217") (name "unconnected-(J3-Pad103)") (class "Default")
      (node (ref "J3") (pin "103") (pinfunction "103_103") (pintype "passive"))
    )
    (net (code "218") (name "unconnected-(J3-Pad104)") (class "Default")
      (node (ref "J3") (pin "104") (pinfunction "104_104") (pintype "passive"))
    )
    (net (code "219") (name "unconnected-(J3-Pad105)") (class "Default")
      (node (ref "J3") (pin "105") (pinfunction "105_105") (pintype "passive"))
    )
    (net (code "220") (name "unconnected-(J3-Pad106)") (class "Default")
      (node (ref "J3") (pin "106") (pinfunction "106_106") (pintype "passive"))
    )
    (net (code "221") (name "unconnected-(J3-Pad107)") (class "Default")
      (node (ref "J3") (pin "107") (pinfunction "107_107") (pintype "passive"))
    )
    (net (code "222") (name "unconnected-(J3-Pad108)") (class "Default")
      (node (ref "J3") (pin "108") (pinfunction "108_108") (pintype "passive"))
    )
    (net (code "223") (name "unconnected-(J3-Pad109)") (class "Default")
      (node (ref "J3") (pin "109") (pinfunction "109_109") (pintype "passive"))
    )
    (net (code "224") (name "unconnected-(J3-Pad110)") (class "Default")
      (node (ref "J3") (pin "110") (pinfunction "110_110") (pintype "passive"))
    )
    (net (code "225") (name "unconnected-(J3-Pad111)") (class "Default")
      (node (ref "J3") (pin "111") (pinfunction "111_111") (pintype "passive"))
    )
    (net (code "226") (name "unconnected-(J3-Pad112)") (class "Default")
      (node (ref "J3") (pin "112") (pinfunction "112_112") (pintype "passive"))
    )
    (net (code "227") (name "unconnected-(J3-Pad113)") (class "Default")
      (node (ref "J3") (pin "113") (pinfunction "113_113") (pintype "passive"))
    )
    (net (code "228") (name "unconnected-(J3-Pad114)") (class "Default")
      (node (ref "J3") (pin "114") (pinfunction "114_114") (pintype "passive"))
    )
    (net (code "229") (name "unconnected-(J3-Pad115)") (class "Default")
      (node (ref "J3") (pin "115") (pinfunction "115_115") (pintype "passive"))
    )
    (net (code "230") (name "unconnected-(J3-Pad116)") (class "Default")
      (node (ref "J3") (pin "116") (pinfunction "116_116") (pintype "passive"))
    )
    (net (code "231") (name "unconnected-(J3-Pad117)") (class "Default")
      (node (ref "J3") (pin "117") (pinfunction "117_117") (pintype "passive"))
    )
    (net (code "232") (name "unconnected-(J3-Pad118)") (class "Default")
      (node (ref "J3") (pin "118") (pinfunction "118_118") (pintype "passive"))
    )
    (net (code "233") (name "unconnected-(J3-Pad119)") (class "Default")
      (node (ref "J3") (pin "119") (pinfunction "119_119") (pintype "passive"))
    )
    (net (code "234") (name "unconnected-(J3-Pad120)") (class "Default")
      (node (ref "J3") (pin "120") (pinfunction "120_120") (pintype "passive"))
    )
    (net (code "235") (name "unconnected-(J3-Pad121)") (class "Default")
      (node (ref "J3") (pin "121") (pinfunction "121_121") (pintype "passive"))
    )
    (net (code "236") (name "unconnected-(J3-Pad122)") (class "Default")
      (node (ref "J3") (pin "122") (pinfunction "122_122") (pintype "passive"))
    )
    (net (code "237") (name "unconnected-(J3-Pad123)") (class "Default")
      (node (ref "J3") (pin "123") (pinfunction "123_123") (pintype "passive"))
    )
    (net (code "238") (name "unconnected-(J3-Pad124)") (class "Default")
      (node (ref "J3") (pin "124") (pinfunction "124_124") (pintype "passive"))
    )
    (net (code "239") (name "unconnected-(J3-Pad125)") (class "Default")
      (node (ref "J3") (pin "125") (pinfunction "125_125") (pintype "passive"))
    )
    (net (code "240") (name "unconnected-(J3-Pad126)") (class "Default")
      (node (ref "J3") (pin "126") (pinfunction "126_126") (pintype "passive"))
    )
    (net (code "241") (name "unconnected-(J3-Pad127)") (class "Default")
      (node (ref "J3") (pin "127") (pinfunction "127_127") (pintype "passive"))
    )
    (net (code "242") (name "unconnected-(J3-Pad128)") (class "Default")
      (node (ref "J3") (pin "128") (pinfunction "128_128") (pintype "passive"))
    )
    (net (code "243") (name "unconnected-(J3-Pad129)") (class "Default")
      (node (ref "J3") (pin "129") (pinfunction "129_129") (pintype "passive"))
    )
    (net (code "244") (name "unconnected-(J3-Pad130)") (class "Default")
      (node (ref "J3") (pin "130") (pinfunction "130_130") (pintype "passive"))
    )
    (net (code "245") (name "unconnected-(J3-Pad131)") (class "Default")
      (node (ref "J3") (pin "131") (pinfunction "131_131") (pintype "passive"))
    )
    (net (code "246") (name "unconnected-(J3-Pad132)") (class "Default")
      (node (ref "J3") (pin "132") (pinfunction "132_132") (pintype "passive"))
    )
    (net (code "247") (name "unconnected-(J3-Pad133)") (class "Default")
      (node (ref "J3") (pin "133") (pinfunction "133_133") (pintype "passive"))
    )
    (net (code "248") (name "unconnected-(J3-Pad134)") (class "Default")
      (node (ref "J3") (pin "134") (pinfunction "134_134") (pintype "passive"))
    )
    (net (code "249") (name "unconnected-(J3-Pad135)") (class "Default")
      (node (ref "J3") (pin "135") (pinfunction "135_135") (pintype "passive"))
    )
    (net (code "250") (name "unconnected-(J3-Pad136)") (class "Default")
      (node (ref "J3") (pin "136") (pinfunction "136_136") (pintype "passive"))
    )
    (net (code "251") (name "unconnected-(J3-Pad137)") (class "Default")
      (node (ref "J3") (pin "137") (pinfunction "137_137") (pintype "passive"))
    )
    (net (code "252") (name "unconnected-(J3-Pad138)") (class "Default")
      (node (ref "J3") (pin "138") (pinfunction "138_138") (pintype "passive"))
    )
    (net (code "253") (name "unconnected-(J3-Pad139)") (class "Default")
      (node (ref "J3") (pin "139") (pinfunction "139_139") (pintype "passive"))
    )
    (net (code "254") (name "unconnected-(J3-Pad140)") (class "Default")
      (node (ref "J3") (pin "140") (pinfunction "140_140") (pintype "passive"))
    )
    (net (code "255") (name "unconnected-(J3-Pad141)") (class "Default")
      (node (ref "J3") (pin "141") (pinfunction "141_141") (pintype "passive"))
    )
    (net (code "256") (name "unconnected-(J3-Pad142)") (class "Default")
      (node (ref "J3") (pin "142") (pinfunction "142_142") (pintype "passive"))
    )
    (net (code "257") (name "unconnected-(J3-Pad143)") (class "Default")
      (node (ref "J3") (pin "143") (pinfunction "143_143") (pintype "passive"))
    )
    (net (code "258") (name "unconnected-(J3-Pad144)") (class "Default")
      (node (ref "J3") (pin "144") (pinfunction "144_144") (pintype "passive"))
    )
    (net (code "259") (name "unconnected-(J3-Pad145)") (class "Default")
      (node (ref "J3") (pin "145") (pinfunction "145_145") (pintype "passive"))
    )
    (net (code "260") (name "unconnected-(J3-Pad146)") (class "Default")
      (node (ref "J3") (pin "146") (pinfunction "146_146") (pintype "passive"))
    )
    (net (code "261") (name "unconnected-(J3-Pad147)") (class "Default")
      (node (ref "J3") (pin "147") (pinfunction "147_147") (pintype "passive"))
    )
    (net (code "262") (name "unconnected-(J3-Pad148)") (class "Default")
      (node (ref "J3") (pin "148") (pinfunction "148_148") (pintype "passive"))
    )
    (net (code "263") (name "unconnected-(J3-Pad149)") (class "Default")
      (node (ref "J3") (pin "149") (pinfunction "149_149") (pintype "passive"))
    )
    (net (code "264") (name "unconnected-(J3-Pad150)") (class "Default")
      (node (ref "J3") (pin "150") (pinfunction "150_150") (pintype "passive"))
    )
    (net (code "265") (name "unconnected-(J3-Pad151)") (class "Default")
      (node (ref "J3") (pin "151") (pinfunction "151_151") (pintype "passive"))
    )
    (net (code "266") (name "unconnected-(J3-Pad152)") (class "Default")
      (node (ref "J3") (pin "152") (pinfunction "152_152") (pintype "passive"))
    )
    (net (code "267") (name "unconnected-(J3-Pad153)") (class "Default")
      (node (ref "J3") (pin "153") (pinfunction "153_153") (pintype "passive"))
    )
    (net (code "268") (name "unconnected-(J3-Pad154)") (class "Default")
      (node (ref "J3") (pin "154") (pinfunction "154_154") (pintype "passive"))
    )
    (net (code "269") (name "unconnected-(J3-Pad155)") (class "Default")
      (node (ref "J3") (pin "155") (pinfunction "155_155") (pintype "passive"))
    )
    (net (code "270") (name "unconnected-(J3-Pad156)") (class "Default")
      (node (ref "J3") (pin "156") (pinfunction "156_156") (pintype "passive"))
    )
    (net (code "271") (name "unconnected-(J3-Pad157)") (class "Default")
      (node (ref "J3") (pin "157") (pinfunction "157_157") (pintype "passive"))
    )
    (net (code "272") (name "unconnected-(J3-Pad158)") (class "Default")
      (node (ref "J3") (pin "158") (pinfunction "158_158") (pintype "passive"))
    )
    (net (code "273") (name "unconnected-(J3-Pad159)") (class "Default")
      (node (ref "J3") (pin "159") (pinfunction "159_159") (pintype "passive"))
    )
    (net (code "274") (name "unconnected-(J3-Pad160)") (class "Default")
      (node (ref "J3") (pin "160") (pinfunction "160_160") (pintype "passive"))
    )
    (net (code "275") (name "unconnected-(J3-Pad161)") (class "Default")
      (node (ref "J3") (pin "161") (pinfunction "161_161") (pintype "passive"))
    )
    (net (code "276") (name "unconnected-(J3-Pad162)") (class "Default")
      (node (ref "J3") (pin "162") (pinfunction "162_162") (pintype "passive"))
    )
    (net (code "277") (name "unconnected-(J3-Pad163)") (class "Default")
      (node (ref "J3") (pin "163") (pinfunction "163_163") (pintype "passive"))
    )
    (net (code "278") (name "unconnected-(J3-Pad164)") (class "Default")
      (node (ref "J3") (pin "164") (pinfunction "164_164") (pintype "passive"))
    )
    (net (code "279") (name "unconnected-(J3-Pad165)") (class "Default")
      (node (ref "J3") (pin "165") (pinfunction "165_165") (pintype "passive"))
    )
    (net (code "280") (name "unconnected-(J3-Pad166)") (class "Default")
      (node (ref "J3") (pin "166") (pinfunction "166_166") (pintype "passive"))
    )
    (net (code "281") (name "unconnected-(J3-Pad167)") (class "Default")
      (node (ref "J3") (pin "167") (pinfunction "167_167") (pintype "passive"))
    )
    (net (code "282") (name "unconnected-(J3-Pad168)") (class "Default")
      (node (ref "J3") (pin "168") (pinfunction "168_168") (pintype "passive"))
    )
    (net (code "283") (name "unconnected-(J3-Pad169)") (class "Default")
      (node (ref "J3") (pin "169") (pinfunction "169_169") (pintype "passive"))
    )
    (net (code "284") (name "unconnected-(J3-Pad170)") (class "Default")
      (node (ref "J3") (pin "170") (pinfunction "170_170") (pintype "passive"))
    )
    (net (code "285") (name "unconnected-(J3-Pad171)") (class "Default")
      (node (ref "J3") (pin "171") (pinfunction "171_171") (pintype "passive"))
    )
    (net (code "286") (name "unconnected-(J3-Pad172)") (class "Default")
      (node (ref "J3") (pin "172") (pinfunction "172_172") (pintype "passive"))
    )
    (net (code "287") (name "unconnected-(J3-Pad173)") (class "Default")
      (node (ref "J3") (pin "173") (pinfunction "173_173") (pintype "passive"))
    )
    (net (code "288") (name "unconnected-(J3-Pad174)") (class "Default")
      (node (ref "J3") (pin "174") (pinfunction "174_174") (pintype "passive"))
    )
    (net (code "289") (name "unconnected-(J3-Pad175)") (class "Default")
      (node (ref "J3") (pin "175") (pinfunction "175_175") (pintype "passive"))
    )
    (net (code "290") (name "unconnected-(J3-Pad176)") (class "Default")
      (node (ref "J3") (pin "176") (pinfunction "176_176") (pintype "passive"))
    )
    (net (code "291") (name "unconnected-(J3-Pad177)") (class "Default")
      (node (ref "J3") (pin "177") (pinfunction "177_177") (pintype "passive"))
    )
    (net (code "292") (name "unconnected-(J3-Pad178)") (class "Default")
      (node (ref "J3") (pin "178") (pinfunction "178_178") (pintype "passive"))
    )
    (net (code "293") (name "unconnected-(J3-Pad179)") (class "Default")
      (node (ref "J3") (pin "179") (pinfunction "179_179") (pintype "passive"))
    )
    (net (code "294") (name "unconnected-(J3-Pad180)") (class "Default")
      (node (ref "J3") (pin "180") (pinfunction "180_180") (pintype "passive"))
    )
    (net (code "295") (name "unconnected-(J3-Pad181)") (class "Default")
      (node (ref "J3") (pin "181") (pinfunction "181_181") (pintype "passive"))
    )
    (net (code "296") (name "unconnected-(J3-Pad182)") (class "Default")
      (node (ref "J3") (pin "182") (pinfunction "182_182") (pintype "passive"))
    )
    (net (code "297") (name "unconnected-(J3-Pad183)") (class "Default")
      (node (ref "J3") (pin "183") (pinfunction "183_183") (pintype "passive"))
    )
    (net (code "298") (name "unconnected-(J3-Pad184)") (class "Default")
      (node (ref "J3") (pin "184") (pinfunction "184_184") (pintype "passive"))
    )
    (net (code "299") (name "unconnected-(J3-Pad185)") (class "Default")
      (node (ref "J3") (pin "185") (pinfunction "185_185") (pintype "passive"))
    )
    (net (code "300") (name "unconnected-(J3-Pad186)") (class "Default")
      (node (ref "J3") (pin "186") (pinfunction "186_186") (pintype "passive"))
    )
    (net (code "301") (name "unconnected-(J3-Pad187)") (class "Default")
      (node (ref "J3") (pin "187") (pinfunction "187_187") (pintype "passive"))
    )
    (net (code "302") (name "unconnected-(J3-Pad188)") (class "Default")
      (node (ref "J3") (pin "188") (pinfunction "188_188") (pintype "passive"))
    )
    (net (code "303") (name "unconnected-(J3-Pad189)") (class "Default")
      (node (ref "J3") (pin "189") (pinfunction "189_189") (pintype "passive"))
    )
    (net (code "304") (name "unconnected-(J3-Pad190)") (class "Default")
      (node (ref "J3") (pin "190") (pinfunction "190_190") (pintype "passive"))
    )
    (net (code "305") (name "unconnected-(J3-Pad191)") (class "Default")
      (node (ref "J3") (pin "191") (pinfunction "191_191") (pintype "passive"))
    )
    (net (code "306") (name "unconnected-(J3-Pad192)") (class "Default")
      (node (ref "J3") (pin "192") (pinfunction "192_192") (pintype "passive"))
    )
    (net (code "307") (name "unconnected-(J3-Pad193)") (class "Default")
      (node (ref "J3") (pin "193") (pinfunction "193_193") (pintype "passive"))
    )
    (net (code "308") (name "unconnected-(J3-Pad194)") (class "Default")
      (node (ref "J3") (pin "194") (pinfunction "194_194") (pintype "passive"))
    )
    (net (code "309") (name "unconnected-(J3-Pad195)") (class "Default")
      (node (ref "J3") (pin "195") (pinfunction "195_195") (pintype "passive"))
    )
    (net (code "310") (name "unconnected-(J3-Pad196)") (class "Default")
      (node (ref "J3") (pin "196") (pinfunction "196_196") (pintype "passive"))
    )
    (net (code "311") (name "unconnected-(J3-Pad197)") (class "Default")
      (node (ref "J3") (pin "197") (pinfunction "197_197") (pintype "passive"))
    )
    (net (code "312") (name "unconnected-(J3-Pad198)") (class "Default")
      (node (ref "J3") (pin "198") (pinfunction "198_198") (pintype "passive"))
    )
    (net (code "313") (name "unconnected-(J3-Pad199)") (class "Default")
      (node (ref "J3") (pin "199") (pinfunction "199_199") (pintype "passive"))
    )
    (net (code "314") (name "unconnected-(J3-Pad200)") (class "Default")
      (node (ref "J3") (pin "200") (pinfunction "200_200") (pintype "passive"))
    )
    (net (code "315") (name "unconnected-(J3-Pad201)") (class "Default")
      (node (ref "J3") (pin "201") (pinfunction "201_201") (pintype "passive"))
    )
    (net (code "316") (name "unconnected-(J3-Pad202)") (class "Default")
      (node (ref "J3") (pin "202") (pinfunction "202_202") (pintype "passive"))
    )
    (net (code "317") (name "unconnected-(J3-Pad203)") (class "Default")
      (node (ref "J3") (pin "203") (pinfunction "203_203") (pintype "passive"))
    )
    (net (code "318") (name "unconnected-(J3-Pad204)") (class "Default")
      (node (ref "J3") (pin "204") (pinfunction "204_204") (pintype "passive"))
    )
    (net (code "319") (name "unconnected-(J3-Pad205)") (class "Default")
      (node (ref "J3") (pin "205") (pinfunction "205_205") (pintype "passive"))
    )
    (net (code "320") (name "unconnected-(J3-Pad206)") (class "Default")
      (node (ref "J3") (pin "206") (pinfunction "206_206") (pintype "passive"))
    )
    (net (code "321") (name "unconnected-(J3-Pad207)") (class "Default")
      (node (ref "J3") (pin "207") (pinfunction "207_207") (pintype "passive"))
    )
    (net (code "322") (name "unconnected-(J3-Pad208)") (class "Default")
      (node (ref "J3") (pin "208") (pinfunction "208_208") (pintype "passive"))
    )
    (net (code "323") (name "unconnected-(J3-Pad209)") (class "Default")
      (node (ref "J3") (pin "209") (pinfunction "209_209") (pintype "passive"))
    )
    (net (code "324") (name "unconnected-(J3-Pad210)") (class "Default")
      (node (ref "J3") (pin "210") (pinfunction "210_210") (pintype "passive"))
    )
    (net (code "325") (name "unconnected-(J3-Pad211)") (class "Default")
      (node (ref "J3") (pin "211") (pinfunction "211_211") (pintype "passive"))
    )
    (net (code "326") (name "unconnected-(J3-Pad212)") (class "Default")
      (node (ref "J3") (pin "212") (pinfunction "212_212") (pintype "passive"))
    )
    (net (code "327") (name "unconnected-(J3-Pad213)") (class "Default")
      (node (ref "J3") (pin "213") (pinfunction "213_213") (pintype "passive"))
    )
    (net (code "328") (name "unconnected-(J3-Pad214)") (class "Default")
      (node (ref "J3") (pin "214") (pinfunction "214_214") (pintype "passive"))
    )
    (net (code "329") (name "unconnected-(J3-Pad215)") (class "Default")
      (node (ref "J3") (pin "215") (pinfunction "215_215") (pintype "passive"))
    )
    (net (code "330") (name "unconnected-(J3-Pad216)") (class "Default")
      (node (ref "J3") (pin "216") (pinfunction "216_216") (pintype "passive"))
    )
    (net (code "331") (name "unconnected-(J3-Pad217)") (class "Default")
      (node (ref "J3") (pin "217") (pinfunction "217_217") (pintype "passive"))
    )
    (net (code "332") (name "unconnected-(J3-Pad218)") (class "Default")
      (node (ref "J3") (pin "218") (pinfunction "218_218") (pintype "passive"))
    )
    (net (code "333") (name "unconnected-(J3-Pad219)") (class "Default")
      (node (ref "J3") (pin "219") (pinfunction "219_219") (pintype "passive"))
    )
    (net (code "334") (name "unconnected-(J3-Pad220)") (class "Default")
      (node (ref "J3") (pin "220") (pinfunction "220_220") (pintype "passive"))
    )
    (net (code "335") (name "unconnected-(J3-Pad221)") (class "Default")
      (node (ref "J3") (pin "221") (pinfunction "221_221") (pintype "passive"))
    )
    (net (code "336") (name "unconnected-(J3-Pad222)") (class "Default")
      (node (ref "J3") (pin "222") (pinfunction "222_222") (pintype "passive"))
    )
    (net (code "337") (name "unconnected-(J3-Pad223)") (class "Default")
      (node (ref "J3") (pin "223") (pinfunction "223_223") (pintype "passive"))
    )
    (net (code "338") (name "unconnected-(J3-Pad224)") (class "Default")
      (node (ref "J3") (pin "224") (pinfunction "224_224") (pintype "passive"))
    )
    (net (code "339") (name "unconnected-(J3-Pad225)") (class "Default")
      (node (ref "J3") (pin "225") (pinfunction "225_225") (pintype "passive"))
    )
    (net (code "340") (name "unconnected-(J3-Pad226)") (class "Default")
      (node (ref "J3") (pin "226") (pinfunction "226_226") (pintype "passive"))
    )
    (net (code "341") (name "unconnected-(J3-Pad227)") (class "Default")
      (node (ref "J3") (pin "227") (pinfunction "227_227") (pintype "passive"))
    )
    (net (code "342") (name "unconnected-(J3-Pad228)") (class "Default")
      (node (ref "J3") (pin "228") (pinfunction "228_228") (pintype "passive"))
    )
    (net (code "343") (name "unconnected-(J3-Pad229)") (class "Default")
      (node (ref "J3") (pin "229") (pinfunction "229_229") (pintype "passive"))
    )
    (net (code "344") (name "unconnected-(J3-Pad230)") (class "Default")
      (node (ref "J3") (pin "230") (pinfunction "230_230") (pintype "passive"))
    )
    (net (code "345") (name "unconnected-(J3-Pad231)") (class "Default")
      (node (ref "J3") (pin "231") (pinfunction "231_231") (pintype "passive"))
    )
    (net (code "346") (name "unconnected-(J3-Pad232)") (class "Default")
      (node (ref "J3") (pin "232") (pinfunction "232_232") (pintype "passive"))
    )
    (net (code "347") (name "unconnected-(J3-Pad233)") (class "Default")
      (node (ref "J3") (pin "233") (pinfunction "233_233") (pintype "passive"))
    )
    (net (code "348") (name "unconnected-(J3-Pad234)") (class "Default")
      (node (ref "J3") (pin "234") (pinfunction "234_234") (pintype "passive"))
    )
    (net (code "349") (name "unconnected-(J3-Pad235)") (class "Default")
      (node (ref "J3") (pin "235") (pinfunction "235_235") (pintype "passive"))
    )
    (net (code "350") (name "unconnected-(J3-Pad236)") (class "Default")
      (node (ref "J3") (pin "236") (pinfunction "236_236") (pintype "passive"))
    )
    (net (code "351") (name "unconnected-(J3-Pad237)") (class "Default")
      (node (ref "J3") (pin "237") (pinfunction "237_237") (pintype "passive"))
    )
    (net (code "352") (name "unconnected-(J3-Pad238)") (class "Default")
      (node (ref "J3") (pin "238") (pinfunction "238_238") (pintype "passive"))
    )
    (net (code "353") (name "unconnected-(J3-Pad239)") (class "Default")
      (node (ref "J3") (pin "239") (pinfunction "239_239") (pintype "passive"))
    )
    (net (code "354") (name "unconnected-(J3-Pad240)") (class "Default")
      (node (ref "J3") (pin "240") (pinfunction "240_240") (pintype "passive"))
    )
    (net (code "355") (name "unconnected-(J3-Pad241)") (class "Default")
      (node (ref "J3") (pin "241") (pinfunction "241_241") (pintype "passive"))
    )
    (net (code "356") (name "unconnected-(J3-Pad242)") (class "Default")
      (node (ref "J3") (pin "242") (pinfunction "242_242") (pintype "passive"))
    )
    (net (code "357") (name "unconnected-(J3-Pad243)") (class "Default")
      (node (ref "J3") (pin "243") (pinfunction "243_243") (pintype "passive"))
    )
    (net (code "358") (name "unconnected-(J3-Pad244)") (class "Default")
      (node (ref "J3") (pin "244") (pinfunction "244_244") (pintype "passive"))
    )
    (net (code "359") (name "unconnected-(J3-Pad245)") (class "Default")
      (node (ref "J3") (pin "245") (pinfunction "245_245") (pintype "passive"))
    )
    (net (code "360") (name "unconnected-(J3-Pad246)") (class "Default")
      (node (ref "J3") (pin "246") (pinfunction "246_246") (pintype "passive"))
    )
    (net (code "361") (name "unconnected-(J3-Pad247)") (class "Default")
      (node (ref "J3") (pin "247") (pinfunction "247_247") (pintype "passive"))
    )
    (net (code "362") (name "unconnected-(J3-Pad248)") (class "Default")
      (node (ref "J3") (pin "248") (pinfunction "248_248") (pintype "passive"))
    )
    (net (code "363") (name "unconnected-(J3-Pad249)") (class "Default")
      (node (ref "J3") (pin "249") (pinfunction "249_249") (pintype "passive"))
    )
    (net (code "364") (name "unconnected-(J3-Pad250)") (class "Default")
      (node (ref "J3") (pin "250") (pinfunction "250_250") (pintype "passive"))
    )
    (net (code "365") (name "unconnected-(J3-Pad251)") (class "Default")
      (node (ref "J3") (pin "251") (pinfunction "251_251") (pintype "passive"))
    )
    (net (code "366") (name "unconnected-(J3-Pad252)") (class "Default")
      (node (ref "J3") (pin "252") (pinfunction "252_252") (pintype "passive"))
    )
    (net (code "367") (name "unconnected-(J3-Pad253)") (class "Default")
      (node (ref "J3") (pin "253") (pinfunction "253_253") (pintype "passive"))
    )
    (net (code "368") (name "unconnected-(J3-Pad254)") (class "Default")
      (node (ref "J3") (pin "254") (pinfunction "254_254") (pintype "passive"))
    )
    (net (code "369") (name "unconnected-(J3-Pad255)") (class "Default")
      (node (ref "J3") (pin "255") (pinfunction "255_255") (pintype "passive"))
    )
    (net (code "370") (name "unconnected-(J3-Pad256)") (class "Default")
      (node (ref "J3") (pin "256") (pinfunction "256_256") (pintype "passive"))
    )
    (net (code "371") (name "unconnected-(J3-Pad257)") (class "Default")
      (node (ref "J3") (pin "257") (pinfunction "257_257") (pintype "passive"))
    )
    (net (code "372") (name "unconnected-(J3-Pad258)") (class "Default")
      (node (ref "J3") (pin "258") (pinfunction "258_258") (pintype "passive"))
    )
    (net (code "373") (name "unconnected-(J3-Pad259)") (class "Default")
      (node (ref "J3") (pin "259") (pinfunction "259_259") (pintype "passive"))
    )
    (net (code "374") (name "unconnected-(J3-Pad260)") (class "Default")
      (node (ref "J3") (pin "260") (pinfunction "260_260") (pintype "passive"))
    )
    (net (code "375") (name "unconnected-(J4-Pad1)") (class "Default")
      (node (ref "J4") (pin "1") (pinfunction "1_1") (pintype "passive"))
    )
    (net (code "376") (name "unconnected-(J4-Pad2)") (class "Default")
      (node (ref "J4") (pin "2") (pinfunction "2_2") (pintype "passive"))
    )
    (net (code "377") (name "unconnected-(J4-Pad3)") (class "Default")
      (node (ref "J4") (pin "3") (pinfunction "3_3") (pintype "passive"))
    )
    (net (code "378") (name "unconnected-(J4-Pad4)") (class "Default")
      (node (ref "J4") (pin "4") (pinfunction "4_4") (pintype "passive"))
    )
    (net (code "379") (name "unconnected-(J4-Pad5)") (class "Default")
      (node (ref "J4") (pin "5") (pinfunction "5_5") (pintype "passive"))
    )
    (net (code "380") (name "unconnected-(J4-Pad6)") (class "Default")
      (node (ref "J4") (pin "6") (pinfunction "6_6") (pintype "passive"))
    )
    (net (code "381") (name "unconnected-(J4-Pad7)") (class "Default")
      (node (ref "J4") (pin "7") (pinfunction "7_7") (pintype "passive"))
    )
    (net (code "382") (name "unconnected-(J4-Pad8)") (class "Default")
      (node (ref "J4") (pin "8") (pinfunction "8_8") (pintype "passive"))
    )
    (net (code "383") (name "unconnected-(J4-Pad9)") (class "Default")
      (node (ref "J4") (pin "9") (pinfunction "9_9") (pintype "passive"))
    )
    (net (code "384") (name "unconnected-(J4-Pad10)") (class "Default")
      (node (ref "J4") (pin "10") (pinfunction "10_10") (pintype "passive"))
    )
    (net (code "385") (name "unconnected-(J4-Pad11)") (class "Default")
      (node (ref "J4") (pin "11") (pinfunction "11_11") (pintype "passive"))
    )
    (net (code "386") (name "unconnected-(J4-Pad12)") (class "Default")
      (node (ref "J4") (pin "12") (pinfunction "12_12") (pintype "passive"))
    )
    (net (code "387") (name "unconnected-(J4-Pad13)") (class "Default")
      (node (ref "J4") (pin "13") (pinfunction "13_13") (pintype "passive"))
    )
    (net (code "388") (name "unconnected-(J4-Pad14)") (class "Default")
      (node (ref "J4") (pin "14") (pinfunction "14_14") (pintype "passive"))
    )
    (net (code "389") (name "unconnected-(J4-Pad15)") (class "Default")
      (node (ref "J4") (pin "15") (pinfunction "15_15") (pintype "passive"))
    )
    (net (code "390") (name "unconnected-(J4-Pad16)") (class "Default")
      (node (ref "J4") (pin "16") (pinfunction "16_16") (pintype "passive"))
    )
    (net (code "391") (name "unconnected-(J4-Pad17)") (class "Default")
      (node (ref "J4") (pin "17") (pinfunction "17_17") (pintype "passive"))
    )
    (net (code "392") (name "unconnected-(J4-Pad18)") (class "Default")
      (node (ref "J4") (pin "18") (pinfunction "18_18") (pintype "passive"))
    )
    (net (code "393") (name "unconnected-(J4-Pad19)") (class "Default")
      (node (ref "J4") (pin "19") (pinfunction "19_19") (pintype "passive"))
    )
    (net (code "394") (name "unconnected-(J4-Pad20)") (class "Default")
      (node (ref "J4") (pin "20") (pinfunction "20_20") (pintype "passive"))
    )
    (net (code "395") (name "unconnected-(J4-Pad21)") (class "Default")
      (node (ref "J4") (pin "21") (pinfunction "21_21") (pintype "passive"))
    )
    (net (code "396") (name "unconnected-(J4-Pad22)") (class "Default")
      (node (ref "J4") (pin "22") (pinfunction "22_22") (pintype "passive"))
    )
    (net (code "397") (name "unconnected-(J4-Pad23)") (class "Default")
      (node (ref "J4") (pin "23") (pinfunction "23_23") (pintype "passive"))
    )
    (net (code "398") (name "unconnected-(J4-Pad24)") (class "Default")
      (node (ref "J4") (pin "24") (pinfunction "24_24") (pintype "passive"))
    )
    (net (code "399") (name "unconnected-(J4-Pad25)") (class "Default")
      (node (ref "J4") (pin "25") (pinfunction "25_25") (pintype "passive"))
    )
    (net (code "400") (name "unconnected-(J4-Pad26)") (class "Default")
      (node (ref "J4") (pin "26") (pinfunction "26_26") (pintype "passive"))
    )
    (net (code "401") (name "unconnected-(J4-Pad27)") (class "Default")
      (node (ref "J4") (pin "27") (pinfunction "27_27") (pintype "passive"))
    )
    (net (code "402") (name "unconnected-(J4-Pad28)") (class "Default")
      (node (ref "J4") (pin "28") (pinfunction "28_28") (pintype "passive"))
    )
    (net (code "403") (name "unconnected-(J4-Pad29)") (class "Default")
      (node (ref "J4") (pin "29") (pinfunction "29_29") (pintype "passive"))
    )
    (net (code "404") (name "unconnected-(J4-Pad30)") (class "Default")
      (node (ref "J4") (pin "30") (pinfunction "30_30") (pintype "passive"))
    )
    (net (code "405") (name "unconnected-(J4-Pad31)") (class "Default")
      (node (ref "J4") (pin "31") (pinfunction "31_31") (pintype "passive"))
    )
    (net (code "406") (name "unconnected-(J4-Pad32)") (class "Default")
      (node (ref "J4") (pin "32") (pinfunction "32_32") (pintype "passive"))
    )
    (net (code "407") (name "unconnected-(J4-Pad33)") (class "Default")
      (node (ref "J4") (pin "33") (pinfunction "33_33") (pintype "passive"))
    )
    (net (code "408") (name "unconnected-(J4-Pad34)") (class "Default")
      (node (ref "J4") (pin "34") (pinfunction "34_34") (pintype "passive"))
    )
    (net (code "409") (name "unconnected-(J4-Pad35)") (class "Default")
      (node (ref "J4") (pin "35") (pinfunction "35_35") (pintype "passive"))
    )
    (net (code "410") (name "unconnected-(J4-Pad36)") (class "Default")
      (node (ref "J4") (pin "36") (pinfunction "36_36") (pintype "passive"))
    )
    (net (code "411") (name "unconnected-(J4-Pad37)") (class "Default")
      (node (ref "J4") (pin "37") (pinfunction "37_37") (pintype "passive"))
    )
    (net (code "412") (name "unconnected-(J4-Pad38)") (class "Default")
      (node (ref "J4") (pin "38") (pinfunction "38_38") (pintype "passive"))
    )
    (net (code "413") (name "unconnected-(J4-Pad39)") (class "Default")
      (node (ref "J4") (pin "39") (pinfunction "39_39") (pintype "passive"))
    )
    (net (code "414") (name "unconnected-(J4-Pad40)") (class "Default")
      (node (ref "J4") (pin "40") (pinfunction "40_40") (pintype "passive"))
    )
    (net (code "415") (name "unconnected-(J4-Pad41)") (class "Default")
      (node (ref "J4") (pin "41") (pinfunction "41_41") (pintype "passive"))
    )
    (net (code "416") (name "unconnected-(J4-Pad42)") (class "Default")
      (node (ref "J4") (pin "42") (pinfunction "42_42") (pintype "passive"))
    )
    (net (code "417") (name "unconnected-(J4-Pad43)") (class "Default")
      (node (ref "J4") (pin "43") (pinfunction "43_43") (pintype "passive"))
    )
    (net (code "418") (name "unconnected-(J4-Pad44)") (class "Default")
      (node (ref "J4") (pin "44") (pinfunction "44_44") (pintype "passive"))
    )
    (net (code "419") (name "unconnected-(J4-Pad45)") (class "Default")
      (node (ref "J4") (pin "45") (pinfunction "45_45") (pintype "passive"))
    )
    (net (code "420") (name "unconnected-(J4-Pad46)") (class "Default")
      (node (ref "J4") (pin "46") (pinfunction "46_46") (pintype "passive"))
    )
    (net (code "421") (name "unconnected-(J4-Pad47)") (class "Default")
      (node (ref "J4") (pin "47") (pinfunction "47_47") (pintype "passive"))
    )
    (net (code "422") (name "unconnected-(J4-Pad48)") (class "Default")
      (node (ref "J4") (pin "48") (pinfunction "48_48") (pintype "passive"))
    )
    (net (code "423") (name "unconnected-(J4-Pad49)") (class "Default")
      (node (ref "J4") (pin "49") (pinfunction "49_49") (pintype "passive"))
    )
    (net (code "424") (name "unconnected-(J4-Pad50)") (class "Default")
      (node (ref "J4") (pin "50") (pinfunction "50_50") (pintype "passive"))
    )
    (net (code "425") (name "unconnected-(J4-Pad51)") (class "Default")
      (node (ref "J4") (pin "51") (pinfunction "51_51") (pintype "passive"))
    )
    (net (code "426") (name "unconnected-(J4-Pad52)") (class "Default")
      (node (ref "J4") (pin "52") (pinfunction "52_52") (pintype "passive"))
    )
    (net (code "427") (name "unconnected-(J4-Pad53)") (class "Default")
      (node (ref "J4") (pin "53") (pinfunction "53_53") (pintype "passive"))
    )
    (net (code "428") (name "unconnected-(J4-Pad54)") (class "Default")
      (node (ref "J4") (pin "54") (pinfunction "54_54") (pintype "passive"))
    )
    (net (code "429") (name "unconnected-(J4-Pad55)") (class "Default")
      (node (ref "J4") (pin "55") (pinfunction "55_55") (pintype "passive"))
    )
    (net (code "430") (name "unconnected-(J4-Pad56)") (class "Default")
      (node (ref "J4") (pin "56") (pinfunction "56_56") (pintype "passive"))
    )
    (net (code "431") (name "unconnected-(J4-Pad57)") (class "Default")
      (node (ref "J4") (pin "57") (pinfunction "57_57") (pintype "passive"))
    )
    (net (code "432") (name "unconnected-(J4-Pad58)") (class "Default")
      (node (ref "J4") (pin "58") (pinfunction "58_58") (pintype "passive"))
    )
    (net (code "433") (name "unconnected-(J4-Pad59)") (class "Default")
      (node (ref "J4") (pin "59") (pinfunction "59_59") (pintype "passive"))
    )
    (net (code "434") (name "unconnected-(J4-Pad60)") (class "Default")
      (node (ref "J4") (pin "60") (pinfunction "60_60") (pintype "passive"))
    )
    (net (code "435") (name "unconnected-(J4-Pad61)") (class "Default")
      (node (ref "J4") (pin "61") (pinfunction "61_61") (pintype "passive"))
    )
    (net (code "436") (name "unconnected-(J4-Pad62)") (class "Default")
      (node (ref "J4") (pin "62") (pinfunction "62_62") (pintype "passive"))
    )
    (net (code "437") (name "unconnected-(J4-Pad63)") (class "Default")
      (node (ref "J4") (pin "63") (pinfunction "63_63") (pintype "passive"))
    )
    (net (code "438") (name "unconnected-(J4-Pad64)") (class "Default")
      (node (ref "J4") (pin "64") (pinfunction "64_64") (pintype "passive"))
    )
    (net (code "439") (name "unconnected-(J4-Pad65)") (class "Default")
      (node (ref "J4") (pin "65") (pinfunction "65_65") (pintype "passive"))
    )
    (net (code "440") (name "unconnected-(J4-Pad66)") (class "Default")
      (node (ref "J4") (pin "66") (pinfunction "66_66") (pintype "passive"))
    )
    (net (code "441") (name "unconnected-(J4-Pad67)") (class "Default")
      (node (ref "J4") (pin "67") (pinfunction "67_67") (pintype "passive"))
    )
    (net (code "442") (name "unconnected-(J4-Pad68)") (class "Default")
      (node (ref "J4") (pin "68") (pinfunction "68_68") (pintype "passive"))
    )
    (net (code "443") (name "unconnected-(J4-Pad69)") (class "Default")
      (node (ref "J4") (pin "69") (pinfunction "69_69") (pintype "passive"))
    )
    (net (code "444") (name "unconnected-(J4-Pad70)") (class "Default")
      (node (ref "J4") (pin "70") (pinfunction "70_70") (pintype "passive"))
    )
    (net (code "445") (name "unconnected-(J4-Pad71)") (class "Default")
      (node (ref "J4") (pin "71") (pinfunction "71_71") (pintype "passive"))
    )
    (net (code "446") (name "unconnected-(J4-Pad72)") (class "Default")
      (node (ref "J4") (pin "72") (pinfunction "72_72") (pintype "passive"))
    )
    (net (code "447") (name "unconnected-(J4-Pad73)") (class "Default")
      (node (ref "J4") (pin "73") (pinfunction "73_73") (pintype "passive"))
    )
    (net (code "448") (name "unconnected-(J4-Pad74)") (class "Default")
      (node (ref "J4") (pin "74") (pinfunction "74_74") (pintype "passive"))
    )
    (net (code "449") (name "unconnected-(J4-Pad75)") (class "Default")
      (node (ref "J4") (pin "75") (pinfunction "75_75") (pintype "passive"))
    )
    (net (code "450") (name "unconnected-(J4-Pad76)") (class "Default")
      (node (ref "J4") (pin "76") (pinfunction "76_76") (pintype "passive"))
    )
    (net (code "451") (name "unconnected-(J4-Pad77)") (class "Default")
      (node (ref "J4") (pin "77") (pinfunction "77_77") (pintype "passive"))
    )
    (net (code "452") (name "unconnected-(J4-Pad78)") (class "Default")
      (node (ref "J4") (pin "78") (pinfunction "78_78") (pintype "passive"))
    )
    (net (code "453") (name "unconnected-(J4-Pad79)") (class "Default")
      (node (ref "J4") (pin "79") (pinfunction "79_79") (pintype "passive"))
    )
    (net (code "454") (name "unconnected-(J4-Pad80)") (class "Default")
      (node (ref "J4") (pin "80") (pinfunction "80_80") (pintype "passive"))
    )
    (net (code "455") (name "unconnected-(J4-Pad81)") (class "Default")
      (node (ref "J4") (pin "81") (pinfunction "81_81") (pintype "passive"))
    )
    (net (code "456") (name "unconnected-(J4-Pad82)") (class "Default")
      (node (ref "J4") (pin "82") (pinfunction "82_82") (pintype "passive"))
    )
    (net (code "457") (name "unconnected-(J4-Pad83)") (class "Default")
      (node (ref "J4") (pin "83") (pinfunction "83_83") (pintype "passive"))
    )
    (net (code "458") (name "unconnected-(J4-Pad84)") (class "Default")
      (node (ref "J4") (pin "84") (pinfunction "84_84") (pintype "passive"))
    )
    (net (code "459") (name "unconnected-(J4-Pad85)") (class "Default")
      (node (ref "J4") (pin "85") (pinfunction "85_85") (pintype "passive"))
    )
    (net (code "460") (name "unconnected-(J4-Pad86)") (class "Default")
      (node (ref "J4") (pin "86") (pinfunction "86_86") (pintype "passive"))
    )
    (net (code "461") (name "unconnected-(J4-Pad87)") (class "Default")
      (node (ref "J4") (pin "87") (pinfunction "87_87") (pintype "passive"))
    )
    (net (code "462") (name "unconnected-(J4-Pad88)") (class "Default")
      (node (ref "J4") (pin "88") (pinfunction "88_88") (pintype "passive"))
    )
    (net (code "463") (name "unconnected-(J4-Pad89)") (class "Default")
      (node (ref "J4") (pin "89") (pinfunction "89_89") (pintype "passive"))
    )
    (net (code "464") (name "unconnected-(J4-Pad90)") (class "Default")
      (node (ref "J4") (pin "90") (pinfunction "90_90") (pintype "passive"))
    )
    (net (code "465") (name "unconnected-(J4-Pad91)") (class "Default")
      (node (ref "J4") (pin "91") (pinfunction "91_91") (pintype "passive"))
    )
    (net (code "466") (name "unconnected-(J4-Pad92)") (class "Default")
      (node (ref "J4") (pin "92") (pinfunction "92_92") (pintype "passive"))
    )
    (net (code "467") (name "unconnected-(J4-Pad93)") (class "Default")
      (node (ref "J4") (pin "93") (pinfunction "93_93") (pintype "passive"))
    )
    (net (code "468") (name "unconnected-(J4-Pad94)") (class "Default")
      (node (ref "J4") (pin "94") (pinfunction "94_94") (pintype "passive"))
    )
    (net (code "469") (name "unconnected-(J4-Pad95)") (class "Default")
      (node (ref "J4") (pin "95") (pinfunction "95_95") (pintype "passive"))
    )
    (net (code "470") (name "unconnected-(J4-Pad96)") (class "Default")
      (node (ref "J4") (pin "96") (pinfunction "96_96") (pintype "passive"))
    )
    (net (code "471") (name "unconnected-(J4-Pad97)") (class "Default")
      (node (ref "J4") (pin "97") (pinfunction "97_97") (pintype "passive"))
    )
    (net (code "472") (name "unconnected-(J4-Pad98)") (class "Default")
      (node (ref "J4") (pin "98") (pinfunction "98_98") (pintype "passive"))
    )
    (net (code "473") (name "unconnected-(J4-Pad99)") (class "Default")
      (node (ref "J4") (pin "99") (pinfunction "99_99") (pintype "passive"))
    )
    (net (code "474") (name "unconnected-(J4-Pad100)") (class "Default")
      (node (ref "J4") (pin "100") (pinfunction "100_100") (pintype "passive"))
    )
    (net (code "475") (name "unconnected-(J4-Pad101)") (class "Default")
      (node (ref "J4") (pin "101") (pinfunction "101_101") (pintype "passive"))
    )
    (net (code "476") (name "unconnected-(J4-Pad102)") (class "Default")
      (node (ref "J4") (pin "102") (pinfunction "102_102") (pintype "passive"))
    )
    (net (code "477") (name "unconnected-(J4-Pad103)") (class "Default")
      (node (ref "J4") (pin "103") (pinfunction "103_103") (pintype "passive"))
    )
    (net (code "478") (name "unconnected-(J4-Pad104)") (class "Default")
      (node (ref "J4") (pin "104") (pinfunction "104_104") (pintype "passive"))
    )
    (net (code "479") (name "unconnected-(J4-Pad105)") (class "Default")
      (node (ref "J4") (pin "105") (pinfunction "105_105") (pintype "passive"))
    )
    (net (code "480") (name "unconnected-(J4-Pad106)") (class "Default")
      (node (ref "J4") (pin "106") (pinfunction "106_106") (pintype "passive"))
    )
    (net (code "481") (name "unconnected-(J4-Pad107)") (class "Default")
      (node (ref "J4") (pin "107") (pinfunction "107_107") (pintype "passive"))
    )
    (net (code "482") (name "unconnected-(J4-Pad108)") (class "Default")
      (node (ref "J4") (pin "108") (pinfunction "108_108") (pintype "passive"))
    )
    (net (code "483") (name "unconnected-(J4-Pad109)") (class "Default")
      (node (ref "J4") (pin "109") (pinfunction "109_109") (pintype "passive"))
    )
    (net (code "484") (name "unconnected-(J4-Pad110)") (class "Default")
      (node (ref "J4") (pin "110") (pinfunction "110_110") (pintype "passive"))
    )
    (net (code "485") (name "unconnected-(J4-Pad111)") (class "Default")
      (node (ref "J4") (pin "111") (pinfunction "111_111") (pintype "passive"))
    )
    (net (code "486") (name "unconnected-(J4-Pad112)") (class "Default")
      (node (ref "J4") (pin "112") (pinfunction "112_112") (pintype "passive"))
    )
    (net (code "487") (name "unconnected-(J4-Pad113)") (class "Default")
      (node (ref "J4") (pin "113") (pinfunction "113_113") (pintype "passive"))
    )
    (net (code "488") (name "unconnected-(J4-Pad114)") (class "Default")
      (node (ref "J4") (pin "114") (pinfunction "114_114") (pintype "passive"))
    )
    (net (code "489") (name "unconnected-(J4-Pad115)") (class "Default")
      (node (ref "J4") (pin "115") (pinfunction "115_115") (pintype "passive"))
    )
    (net (code "490") (name "unconnected-(J4-Pad116)") (class "Default")
      (node (ref "J4") (pin "116") (pinfunction "116_116") (pintype "passive"))
    )
    (net (code "491") (name "unconnected-(J4-Pad117)") (class "Default")
      (node (ref "J4") (pin "117") (pinfunction "117_117") (pintype "passive"))
    )
    (net (code "492") (name "unconnected-(J4-Pad118)") (class "Default")
      (node (ref "J4") (pin "118") (pinfunction "118_118") (pintype "passive"))
    )
    (net (code "493") (name "unconnected-(J4-Pad119)") (class "Default")
      (node (ref "J4") (pin "119") (pinfunction "119_119") (pintype "passive"))
    )
    (net (code "494") (name "unconnected-(J4-Pad120)") (class "Default")
      (node (ref "J4") (pin "120") (pinfunction "120_120") (pintype "passive"))
    )
    (net (code "495") (name "unconnected-(J4-Pad121)") (class "Default")
      (node (ref "J4") (pin "121") (pinfunction "121_121") (pintype "passive"))
    )
    (net (code "496") (name "unconnected-(J4-Pad122)") (class "Default")
      (node (ref "J4") (pin "122") (pinfunction "122_122") (pintype "passive"))
    )
    (net (code "497") (name "unconnected-(J4-Pad123)") (class "Default")
      (node (ref "J4") (pin "123") (pinfunction "123_123") (pintype "passive"))
    )
    (net (code "498") (name "unconnected-(J4-Pad124)") (class "Default")
      (node (ref "J4") (pin "124") (pinfunction "124_124") (pintype "passive"))
    )
    (net (code "499") (name "unconnected-(J4-Pad125)") (class "Default")
      (node (ref "J4") (pin "125") (pinfunction "125_125") (pintype "passive"))
    )
    (net (code "500") (name "unconnected-(J4-Pad126)") (class "Default")
      (node (ref "J4") (pin "126") (pinfunction "126_126") (pintype "passive"))
    )
    (net (code "501") (name "unconnected-(J4-Pad127)") (class "Default")
      (node (ref "J4") (pin "127") (pinfunction "127_127") (pintype "passive"))
    )
    (net (code "502") (name "unconnected-(J4-Pad128)") (class "Default")
      (node (ref "J4") (pin "128") (pinfunction "128_128") (pintype "passive"))
    )
    (net (code "503") (name "unconnected-(J4-Pad129)") (class "Default")
      (node (ref "J4") (pin "129") (pinfunction "129_129") (pintype "passive"))
    )
    (net (code "504") (name "unconnected-(J4-Pad130)") (class "Default")
      (node (ref "J4") (pin "130") (pinfunction "130_130") (pintype "passive"))
    )
    (net (code "505") (name "unconnected-(J4-Pad131)") (class "Default")
      (node (ref "J4") (pin "131") (pinfunction "131_131") (pintype "passive"))
    )
    (net (code "506") (name "unconnected-(J4-Pad132)") (class "Default")
      (node (ref "J4") (pin "132") (pinfunction "132_132") (pintype "passive"))
    )
    (net (code "507") (name "unconnected-(J4-Pad133)") (class "Default")
      (node (ref "J4") (pin "133") (pinfunction "133_133") (pintype "passive"))
    )
    (net (code "508") (name "unconnected-(J4-Pad134)") (class "Default")
      (node (ref "J4") (pin "134") (pinfunction "134_134") (pintype "passive"))
    )
    (net (code "509") (name "unconnected-(J4-Pad135)") (class "Default")
      (node (ref "J4") (pin "135") (pinfunction "135_135") (pintype "passive"))
    )
    (net (code "510") (name "unconnected-(J4-Pad136)") (class "Default")
      (node (ref "J4") (pin "136") (pinfunction "136_136") (pintype "passive"))
    )
    (net (code "511") (name "unconnected-(J4-Pad137)") (class "Default")
      (node (ref "J4") (pin "137") (pinfunction "137_137") (pintype "passive"))
    )
    (net (code "512") (name "unconnected-(J4-Pad138)") (class "Default")
      (node (ref "J4") (pin "138") (pinfunction "138_138") (pintype "passive"))
    )
    (net (code "513") (name "unconnected-(J4-Pad139)") (class "Default")
      (node (ref "J4") (pin "139") (pinfunction "139_139") (pintype "passive"))
    )
    (net (code "514") (name "unconnected-(J4-Pad140)") (class "Default")
      (node (ref "J4") (pin "140") (pinfunction "140_140") (pintype "passive"))
    )
    (net (code "515") (name "unconnected-(J4-Pad141)") (class "Default")
      (node (ref "J4") (pin "141") (pinfunction "141_141") (pintype "passive"))
    )
    (net (code "516") (name "unconnected-(J4-Pad142)") (class "Default")
      (node (ref "J4") (pin "142") (pinfunction "142_142") (pintype "passive"))
    )
    (net (code "517") (name "unconnected-(J4-Pad143)") (class "Default")
      (node (ref "J4") (pin "143") (pinfunction "143_143") (pintype "passive"))
    )
    (net (code "518") (name "unconnected-(J4-Pad144)") (class "Default")
      (node (ref "J4") (pin "144") (pinfunction "144_144") (pintype "passive"))
    )
    (net (code "519") (name "unconnected-(J4-Pad145)") (class "Default")
      (node (ref "J4") (pin "145") (pinfunction "145_145") (pintype "passive"))
    )
    (net (code "520") (name "unconnected-(J4-Pad146)") (class "Default")
      (node (ref "J4") (pin "146") (pinfunction "146_146") (pintype "passive"))
    )
    (net (code "521") (name "unconnected-(J4-Pad147)") (class "Default")
      (node (ref "J4") (pin "147") (pinfunction "147_147") (pintype "passive"))
    )
    (net (code "522") (name "unconnected-(J4-Pad148)") (class "Default")
      (node (ref "J4") (pin "148") (pinfunction "148_148") (pintype "passive"))
    )
    (net (code "523") (name "unconnected-(J4-Pad149)") (class "Default")
      (node (ref "J4") (pin "149") (pinfunction "149_149") (pintype "passive"))
    )
    (net (code "524") (name "unconnected-(J4-Pad150)") (class "Default")
      (node (ref "J4") (pin "150") (pinfunction "150_150") (pintype "passive"))
    )
    (net (code "525") (name "unconnected-(J4-Pad151)") (class "Default")
      (node (ref "J4") (pin "151") (pinfunction "151_151") (pintype "passive"))
    )
    (net (code "526") (name "unconnected-(J4-Pad152)") (class "Default")
      (node (ref "J4") (pin "152") (pinfunction "152_152") (pintype "passive"))
    )
    (net (code "527") (name "unconnected-(J4-Pad153)") (class "Default")
      (node (ref "J4") (pin "153") (pinfunction "153_153") (pintype "passive"))
    )
    (net (code "528") (name "unconnected-(J4-Pad154)") (class "Default")
      (node (ref "J4") (pin "154") (pinfunction "154_154") (pintype "passive"))
    )
    (net (code "529") (name "unconnected-(J4-Pad155)") (class "Default")
      (node (ref "J4") (pin "155") (pinfunction "155_155") (pintype "passive"))
    )
    (net (code "530") (name "unconnected-(J4-Pad156)") (class "Default")
      (node (ref "J4") (pin "156") (pinfunction "156_156") (pintype "passive"))
    )
    (net (code "531") (name "unconnected-(J4-Pad157)") (class "Default")
      (node (ref "J4") (pin "157") (pinfunction "157_157") (pintype "passive"))
    )
    (net (code "532") (name "unconnected-(J4-Pad158)") (class "Default")
      (node (ref "J4") (pin "158") (pinfunction "158_158") (pintype "passive"))
    )
    (net (code "533") (name "unconnected-(J4-Pad159)") (class "Default")
      (node (ref "J4") (pin "159") (pinfunction "159_159") (pintype "passive"))
    )
    (net (code "534") (name "unconnected-(J4-Pad160)") (class "Default")
      (node (ref "J4") (pin "160") (pinfunction "160_160") (pintype "passive"))
    )
    (net (code "535") (name "unconnected-(J4-Pad161)") (class "Default")
      (node (ref "J4") (pin "161") (pinfunction "161_161") (pintype "passive"))
    )
    (net (code "536") (name "unconnected-(J4-Pad162)") (class "Default")
      (node (ref "J4") (pin "162") (pinfunction "162_162") (pintype "passive"))
    )
    (net (code "537") (name "unconnected-(J4-Pad163)") (class "Default")
      (node (ref "J4") (pin "163") (pinfunction "163_163") (pintype "passive"))
    )
    (net (code "538") (name "unconnected-(J4-Pad164)") (class "Default")
      (node (ref "J4") (pin "164") (pinfunction "164_164") (pintype "passive"))
    )
    (net (code "539") (name "unconnected-(J4-Pad165)") (class "Default")
      (node (ref "J4") (pin "165") (pinfunction "165_165") (pintype "passive"))
    )
    (net (code "540") (name "unconnected-(J4-Pad166)") (class "Default")
      (node (ref "J4") (pin "166") (pinfunction "166_166") (pintype "passive"))
    )
    (net (code "541") (name "unconnected-(J4-Pad167)") (class "Default")
      (node (ref "J4") (pin "167") (pinfunction "167_167") (pintype "passive"))
    )
    (net (code "542") (name "unconnected-(J4-Pad168)") (class "Default")
      (node (ref "J4") (pin "168") (pinfunction "168_168") (pintype "passive"))
    )
    (net (code "543") (name "unconnected-(J4-Pad169)") (class "Default")
      (node (ref "J4") (pin "169") (pinfunction "169_169") (pintype "passive"))
    )
    (net (code "544") (name "unconnected-(J4-Pad170)") (class "Default")
      (node (ref "J4") (pin "170") (pinfunction "170_170") (pintype "passive"))
    )
    (net (code "545") (name "unconnected-(J4-Pad171)") (class "Default")
      (node (ref "J4") (pin "171") (pinfunction "171_171") (pintype "passive"))
    )
    (net (code "546") (name "unconnected-(J4-Pad172)") (class "Default")
      (node (ref "J4") (pin "172") (pinfunction "172_172") (pintype "passive"))
    )
    (net (code "547") (name "unconnected-(J4-Pad173)") (class "Default")
      (node (ref "J4") (pin "173") (pinfunction "173_173") (pintype "passive"))
    )
    (net (code "548") (name "unconnected-(J4-Pad174)") (class "Default")
      (node (ref "J4") (pin "174") (pinfunction "174_174") (pintype "passive"))
    )
    (net (code "549") (name "unconnected-(J4-Pad175)") (class "Default")
      (node (ref "J4") (pin "175") (pinfunction "175_175") (pintype "passive"))
    )
    (net (code "550") (name "unconnected-(J4-Pad176)") (class "Default")
      (node (ref "J4") (pin "176") (pinfunction "176_176") (pintype "passive"))
    )
    (net (code "551") (name "unconnected-(J4-Pad177)") (class "Default")
      (node (ref "J4") (pin "177") (pinfunction "177_177") (pintype "passive"))
    )
    (net (code "552") (name "unconnected-(J4-Pad178)") (class "Default")
      (node (ref "J4") (pin "178") (pinfunction "178_178") (pintype "passive"))
    )
    (net (code "553") (name "unconnected-(J4-Pad179)") (class "Default")
      (node (ref "J4") (pin "179") (pinfunction "179_179") (pintype "passive"))
    )
    (net (code "554") (name "unconnected-(J4-Pad180)") (class "Default")
      (node (ref "J4") (pin "180") (pinfunction "180_180") (pintype "passive"))
    )
    (net (code "555") (name "unconnected-(J4-Pad181)") (class "Default")
      (node (ref "J4") (pin "181") (pinfunction "181_181") (pintype "passive"))
    )
    (net (code "556") (name "unconnected-(J4-Pad182)") (class "Default")
      (node (ref "J4") (pin "182") (pinfunction "182_182") (pintype "passive"))
    )
    (net (code "557") (name "unconnected-(J4-Pad183)") (class "Default")
      (node (ref "J4") (pin "183") (pinfunction "183_183") (pintype "passive"))
    )
    (net (code "558") (name "unconnected-(J4-Pad184)") (class "Default")
      (node (ref "J4") (pin "184") (pinfunction "184_184") (pintype "passive"))
    )
    (net (code "559") (name "unconnected-(J4-Pad185)") (class "Default")
      (node (ref "J4") (pin "185") (pinfunction "185_185") (pintype "passive"))
    )
    (net (code "560") (name "unconnected-(J4-Pad186)") (class "Default")
      (node (ref "J4") (pin "186") (pinfunction "186_186") (pintype "passive"))
    )
    (net (code "561") (name "unconnected-(J4-Pad187)") (class "Default")
      (node (ref "J4") (pin "187") (pinfunction "187_187") (pintype "passive"))
    )
    (net (code "562") (name "unconnected-(J4-Pad188)") (class "Default")
      (node (ref "J4") (pin "188") (pinfunction "188_188") (pintype "passive"))
    )
    (net (code "563") (name "unconnected-(J4-Pad189)") (class "Default")
      (node (ref "J4") (pin "189") (pinfunction "189_189") (pintype "passive"))
    )
    (net (code "564") (name "unconnected-(J4-Pad190)") (class "Default")
      (node (ref "J4") (pin "190") (pinfunction "190_190") (pintype "passive"))
    )
    (net (code "565") (name "unconnected-(J4-Pad191)") (class "Default")
      (node (ref "J4") (pin "191") (pinfunction "191_191") (pintype "passive"))
    )
    (net (code "566") (name "unconnected-(J4-Pad192)") (class "Default")
      (node (ref "J4") (pin "192") (pinfunction "192_192") (pintype "passive"))
    )
    (net (code "567") (name "unconnected-(J4-Pad193)") (class "Default")
      (node (ref "J4") (pin "193") (pinfunction "193_193") (pintype "passive"))
    )
    (net (code "568") (name "unconnected-(J4-Pad194)") (class "Default")
      (node (ref "J4") (pin "194") (pinfunction "194_194") (pintype "passive"))
    )
    (net (code "569") (name "unconnected-(J4-Pad195)") (class "Default")
      (node (ref "J4") (pin "195") (pinfunction "195_195") (pintype "passive"))
    )
    (net (code "570") (name "unconnected-(J4-Pad196)") (class "Default")
      (node (ref "J4") (pin "196") (pinfunction "196_196") (pintype "passive"))
    )
    (net (code "571") (name "unconnected-(J4-Pad197)") (class "Default")
      (node (ref "J4") (pin "197") (pinfunction "197_197") (pintype "passive"))
    )
    (net (code "572") (name "unconnected-(J4-Pad198)") (class "Default")
      (node (ref "J4") (pin "198") (pinfunction "198_198") (pintype "passive"))
    )
    (net (code "573") (name "unconnected-(J4-Pad199)") (class "Default")
      (node (ref "J4") (pin "199") (pinfunction "199_199") (pintype "passive"))
    )
    (net (code "574") (name "unconnected-(J4-Pad200)") (class "Default")
      (node (ref "J4") (pin "200") (pinfunction "200_200") (pintype "passive"))
    )
    (net (code "575") (name "unconnected-(J4-Pad201)") (class "Default")
      (node (ref "J4") (pin "201") (pinfunction "201_201") (pintype "passive"))
    )
    (net (code "576") (name "unconnected-(J4-Pad202)") (class "Default")
      (node (ref "J4") (pin "202") (pinfunction "202_202") (pintype "passive"))
    )
    (net (code "577") (name "unconnected-(J4-Pad203)") (class "Default")
      (node (ref "J4") (pin "203") (pinfunction "203_203") (pintype "passive"))
    )
    (net (code "578") (name "unconnected-(J4-Pad204)") (class "Default")
      (node (ref "J4") (pin "204") (pinfunction "204_204") (pintype "passive"))
    )
    (net (code "579") (name "unconnected-(J4-Pad205)") (class "Default")
      (node (ref "J4") (pin "205") (pinfunction "205_205") (pintype "passive"))
    )
    (net (code "580") (name "unconnected-(J4-Pad206)") (class "Default")
      (node (ref "J4") (pin "206") (pinfunction "206_206") (pintype "passive"))
    )
    (net (code "581") (name "unconnected-(J4-Pad207)") (class "Default")
      (node (ref "J4") (pin "207") (pinfunction "207_207") (pintype "passive"))
    )
    (net (code "582") (name "unconnected-(J4-Pad208)") (class "Default")
      (node (ref "J4") (pin "208") (pinfunction "208_208") (pintype "passive"))
    )
    (net (code "583") (name "unconnected-(J4-Pad209)") (class "Default")
      (node (ref "J4") (pin "209") (pinfunction "209_209") (pintype "passive"))
    )
    (net (code "584") (name "unconnected-(J4-Pad210)") (class "Default")
      (node (ref "J4") (pin "210") (pinfunction "210_210") (pintype "passive"))
    )
    (net (code "585") (name "unconnected-(J4-Pad211)") (class "Default")
      (node (ref "J4") (pin "211") (pinfunction "211_211") (pintype "passive"))
    )
    (net (code "586") (name "unconnected-(J4-Pad212)") (class "Default")
      (node (ref "J4") (pin "212") (pinfunction "212_212") (pintype "passive"))
    )
    (net (code "587") (name "unconnected-(J4-Pad213)") (class "Default")
      (node (ref "J4") (pin "213") (pinfunction "213_213") (pintype "passive"))
    )
    (net (code "588") (name "unconnected-(J4-Pad214)") (class "Default")
      (node (ref "J4") (pin "214") (pinfunction "214_214") (pintype "passive"))
    )
    (net (code "589") (name "unconnected-(J4-Pad215)") (class "Default")
      (node (ref "J4") (pin "215") (pinfunction "215_215") (pintype "passive"))
    )
    (net (code "590") (name "unconnected-(J4-Pad216)") (class "Default")
      (node (ref "J4") (pin "216") (pinfunction "216_216") (pintype "passive"))
    )
    (net (code "591") (name "unconnected-(J4-Pad217)") (class "Default")
      (node (ref "J4") (pin "217") (pinfunction "217_217") (pintype "passive"))
    )
    (net (code "592") (name "unconnected-(J4-Pad218)") (class "Default")
      (node (ref "J4") (pin "218") (pinfunction "218_218") (pintype "passive"))
    )
    (net (code "593") (name "unconnected-(J4-Pad219)") (class "Default")
      (node (ref "J4") (pin "219") (pinfunction "219_219") (pintype "passive"))
    )
    (net (code "594") (name "unconnected-(J4-Pad220)") (class "Default")
      (node (ref "J4") (pin "220") (pinfunction "220_220") (pintype "passive"))
    )
    (net (code "595") (name "unconnected-(J4-Pad221)") (class "Default")
      (node (ref "J4") (pin "221") (pinfunction "221_221") (pintype "passive"))
    )
    (net (code "596") (name "unconnected-(J4-Pad222)") (class "Default")
      (node (ref "J4") (pin "222") (pinfunction "222_222") (pintype "passive"))
    )
    (net (code "597") (name "unconnected-(J4-Pad223)") (class "Default")
      (node (ref "J4") (pin "223") (pinfunction "223_223") (pintype "passive"))
    )
    (net (code "598") (name "unconnected-(J4-Pad224)") (class "Default")
      (node (ref "J4") (pin "224") (pinfunction "224_224") (pintype "passive"))
    )
    (net (code "599") (name "unconnected-(J4-Pad225)") (class "Default")
      (node (ref "J4") (pin "225") (pinfunction "225_225") (pintype "passive"))
    )
    (net (code "600") (name "unconnected-(J4-Pad226)") (class "Default")
      (node (ref "J4") (pin "226") (pinfunction "226_226") (pintype "passive"))
    )
    (net (code "601") (name "unconnected-(J4-Pad227)") (class "Default")
      (node (ref "J4") (pin "227") (pinfunction "227_227") (pintype "passive"))
    )
    (net (code "602") (name "unconnected-(J4-Pad228)") (class "Default")
      (node (ref "J4") (pin "228") (pinfunction "228_228") (pintype "passive"))
    )
    (net (code "603") (name "unconnected-(J4-Pad229)") (class "Default")
      (node (ref "J4") (pin "229") (pinfunction "229_229") (pintype "passive"))
    )
    (net (code "604") (name "unconnected-(J4-Pad230)") (class "Default")
      (node (ref "J4") (pin "230") (pinfunction "230_230") (pintype "passive"))
    )
    (net (code "605") (name "unconnected-(J4-Pad231)") (class "Default")
      (node (ref "J4") (pin "231") (pinfunction "231_231") (pintype "passive"))
    )
    (net (code "606") (name "unconnected-(J4-Pad232)") (class "Default")
      (node (ref "J4") (pin "232") (pinfunction "232_232") (pintype "passive"))
    )
    (net (code "607") (name "unconnected-(J4-Pad233)") (class "Default")
      (node (ref "J4") (pin "233") (pinfunction "233_233") (pintype "passive"))
    )
    (net (code "608") (name "unconnected-(J4-Pad234)") (class "Default")
      (node (ref "J4") (pin "234") (pinfunction "234_234") (pintype "passive"))
    )
    (net (code "609") (name "unconnected-(J4-Pad235)") (class "Default")
      (node (ref "J4") (pin "235") (pinfunction "235_235") (pintype "passive"))
    )
    (net (code "610") (name "unconnected-(J4-Pad236)") (class "Default")
      (node (ref "J4") (pin "236") (pinfunction "236_236") (pintype "passive"))
    )
    (net (code "611") (name "unconnected-(J4-Pad237)") (class "Default")
      (node (ref "J4") (pin "237") (pinfunction "237_237") (pintype "passive"))
    )
    (net (code "612") (name "unconnected-(J4-Pad238)") (class "Default")
      (node (ref "J4") (pin "238") (pinfunction "238_238") (pintype "passive"))
    )
    (net (code "613") (name "unconnected-(J4-Pad239)") (class "Default")
      (node (ref "J4") (pin "239") (pinfunction "239_239") (pintype "passive"))
    )
    (net (code "614") (name "unconnected-(J4-Pad240)") (class "Default")
      (node (ref "J4") (pin "240") (pinfunction "240_240") (pintype "passive"))
    )
    (net (code "615") (name "unconnected-(J4-Pad241)") (class "Default")
      (node (ref "J4") (pin "241") (pinfunction "241_241") (pintype "passive"))
    )
    (net (code "616") (name "unconnected-(J4-Pad242)") (class "Default")
      (node (ref "J4") (pin "242") (pinfunction "242_242") (pintype "passive"))
    )
    (net (code "617") (name "unconnected-(J4-Pad243)") (class "Default")
      (node (ref "J4") (pin "243") (pinfunction "243_243") (pintype "passive"))
    )
    (net (code "618") (name "unconnected-(J4-Pad244)") (class "Default")
      (node (ref "J4") (pin "244") (pinfunction "244_244") (pintype "passive"))
    )
    (net (code "619") (name "unconnected-(J4-Pad245)") (class "Default")
      (node (ref "J4") (pin "245") (pinfunction "245_245") (pintype "passive"))
    )
    (net (code "620") (name "unconnected-(J4-Pad246)") (class "Default")
      (node (ref "J4") (pin "246") (pinfunction "246_246") (pintype "passive"))
    )
    (net (code "621") (name "unconnected-(J4-Pad247)") (class "Default")
      (node (ref "J4") (pin "247") (pinfunction "247_247") (pintype "passive"))
    )
    (net (code "622") (name "unconnected-(J4-Pad248)") (class "Default")
      (node (ref "J4") (pin "248") (pinfunction "248_248") (pintype "passive"))
    )
    (net (code "623") (name "unconnected-(J4-Pad249)") (class "Default")
      (node (ref "J4") (pin "249") (pinfunction "249_249") (pintype "passive"))
    )
    (net (code "624") (name "unconnected-(J4-Pad250)") (class "Default")
      (node (ref "J4") (pin "250") (pinfunction "250_250") (pintype "passive"))
    )
    (net (code "625") (name "unconnected-(J4-Pad251)") (class "Default")
      (node (ref "J4") (pin "251") (pinfunction "251_251") (pintype "passive"))
    )
    (net (code "626") (name "unconnected-(J4-Pad252)") (class "Default")
      (node (ref "J4") (pin "252") (pinfunction "252_252") (pintype "passive"))
    )
    (net (code "627") (name "unconnected-(J4-Pad253)") (class "Default")
      (node (ref "J4") (pin "253") (pinfunction "253_253") (pintype "passive"))
    )
    (net (code "628") (name "unconnected-(J4-Pad254)") (class "Default")
      (node (ref "J4") (pin "254") (pinfunction "254_254") (pintype "passive"))
    )
    (net (code "629") (name "unconnected-(J4-Pad255)") (class "Default")
      (node (ref "J4") (pin "255") (pinfunction "255_255") (pintype "passive"))
    )
    (net (code "630") (name "unconnected-(J4-Pad256)") (class "Default")
      (node (ref "J4") (pin "256") (pinfunction "256_256") (pintype "passive"))
    )
    (net (code "631") (name "unconnected-(J4-Pad257)") (class "Default")
      (node (ref "J4") (pin "257") (pinfunction "257_257") (pintype "passive"))
    )
    (net (code "632") (name "unconnected-(J4-Pad258)") (class "Default")
      (node (ref "J4") (pin "258") (pinfunction "258_258") (pintype "passive"))
    )
    (net (code "633") (name "unconnected-(J4-Pad259)") (class "Default")
      (node (ref "J4") (pin "259") (pinfunction "259_259") (pintype "passive"))
    )
    (net (code "634") (name "unconnected-(J4-Pad260)") (class "Default")
      (node (ref "J4") (pin "260") (pinfunction "260_260") (pintype "passive"))
    )
    (net (code "635") (name "unconnected-(J5-Pad1)") (class "Default")
      (node (ref "J5") (pin "1") (pinfunction "1_1") (pintype "passive"))
    )
    (net (code "636") (name "unconnected-(J5-Pad2)") (class "Default")
      (node (ref "J5") (pin "2") (pinfunction "2_2") (pintype "passive"))
    )
    (net (code "637") (name "unconnected-(J5-Pad3)") (class "Default")
      (node (ref "J5") (pin "3") (pinfunction "3_3") (pintype "passive"))
    )
    (net (code "638") (name "unconnected-(J5-Pad4)") (class "Default")
      (node (ref "J5") (pin "4") (pinfunction "4_4") (pintype "passive"))
    )
    (net (code "639") (name "unconnected-(J5-Pad5)") (class "Default")
      (node (ref "J5") (pin "5") (pinfunction "5_5") (pintype "passive"))
    )
    (net (code "640") (name "unconnected-(J5-Pad6)") (class "Default")
      (node (ref "J5") (pin "6") (pinfunction "6_6") (pintype "passive"))
    )
    (net (code "641") (name "unconnected-(J5-Pad7)") (class "Default")
      (node (ref "J5") (pin "7") (pinfunction "7_7") (pintype "passive"))
    )
    (net (code "642") (name "unconnected-(J5-Pad8)") (class "Default")
      (node (ref "J5") (pin "8") (pinfunction "8_8") (pintype "passive"))
    )
    (net (code "643") (name "unconnected-(J5-Pad9)") (class "Default")
      (node (ref "J5") (pin "9") (pinfunction "9_9") (pintype "passive"))
    )
    (net (code "644") (name "unconnected-(J5-Pad10)") (class "Default")
      (node (ref "J5") (pin "10") (pinfunction "10_10") (pintype "passive"))
    )
    (net (code "645") (name "unconnected-(J5-Pad11)") (class "Default")
      (node (ref "J5") (pin "11") (pinfunction "11_11") (pintype "passive"))
    )
    (net (code "646") (name "unconnected-(J5-Pad12)") (class "Default")
      (node (ref "J5") (pin "12") (pinfunction "12_12") (pintype "passive"))
    )
    (net (code "647") (name "unconnected-(J5-Pad13)") (class "Default")
      (node (ref "J5") (pin "13") (pinfunction "13_13") (pintype "passive"))
    )
    (net (code "648") (name "unconnected-(J5-Pad14)") (class "Default")
      (node (ref "J5") (pin "14") (pinfunction "14_14") (pintype "passive"))
    )
    (net (code "649") (name "unconnected-(J5-Pad15)") (class "Default")
      (node (ref "J5") (pin "15") (pinfunction "15_15") (pintype "passive"))
    )
    (net (code "650") (name "unconnected-(J5-Pad16)") (class "Default")
      (node (ref "J5") (pin "16") (pinfunction "16_16") (pintype "passive"))
    )
    (net (code "651") (name "unconnected-(J5-Pad17)") (class "Default")
      (node (ref "J5") (pin "17") (pinfunction "17_17") (pintype "passive"))
    )
    (net (code "652") (name "unconnected-(J5-Pad18)") (class "Default")
      (node (ref "J5") (pin "18") (pinfunction "18_18") (pintype "passive"))
    )
    (net (code "653") (name "unconnected-(J5-Pad19)") (class "Default")
      (node (ref "J5") (pin "19") (pinfunction "19_19") (pintype "passive"))
    )
    (net (code "654") (name "unconnected-(J5-Pad20)") (class "Default")
      (node (ref "J5") (pin "20") (pinfunction "20_20") (pintype "passive"))
    )
    (net (code "655") (name "unconnected-(J5-Pad21)") (class "Default")
      (node (ref "J5") (pin "21") (pinfunction "21_21") (pintype "passive"))
    )
    (net (code "656") (name "unconnected-(J5-Pad22)") (class "Default")
      (node (ref "J5") (pin "22") (pinfunction "22_22") (pintype "passive"))
    )
    (net (code "657") (name "unconnected-(J5-Pad23)") (class "Default")
      (node (ref "J5") (pin "23") (pinfunction "23_23") (pintype "passive"))
    )
    (net (code "658") (name "unconnected-(J5-Pad24)") (class "Default")
      (node (ref "J5") (pin "24") (pinfunction "24_24") (pintype "passive"))
    )
    (net (code "659") (name "unconnected-(J5-Pad25)") (class "Default")
      (node (ref "J5") (pin "25") (pinfunction "25_25") (pintype "passive"))
    )
    (net (code "660") (name "unconnected-(J5-Pad26)") (class "Default")
      (node (ref "J5") (pin "26") (pinfunction "26_26") (pintype "passive"))
    )
    (net (code "661") (name "unconnected-(J5-Pad27)") (class "Default")
      (node (ref "J5") (pin "27") (pinfunction "27_27") (pintype "passive"))
    )
    (net (code "662") (name "unconnected-(J5-Pad28)") (class "Default")
      (node (ref "J5") (pin "28") (pinfunction "28_28") (pintype "passive"))
    )
    (net (code "663") (name "unconnected-(J5-Pad29)") (class "Default")
      (node (ref "J5") (pin "29") (pinfunction "29_29") (pintype "passive"))
    )
    (net (code "664") (name "unconnected-(J5-Pad30)") (class "Default")
      (node (ref "J5") (pin "30") (pinfunction "30_30") (pintype "passive"))
    )
    (net (code "665") (name "unconnected-(J5-Pad31)") (class "Default")
      (node (ref "J5") (pin "31") (pinfunction "31_31") (pintype "passive"))
    )
    (net (code "666") (name "unconnected-(J5-Pad32)") (class "Default")
      (node (ref "J5") (pin "32") (pinfunction "32_32") (pintype "passive"))
    )
    (net (code "667") (name "unconnected-(J5-Pad33)") (class "Default")
      (node (ref "J5") (pin "33") (pinfunction "33_33") (pintype "passive"))
    )
    (net (code "668") (name "unconnected-(J5-Pad34)") (class "Default")
      (node (ref "J5") (pin "34") (pinfunction "34_34") (pintype "passive"))
    )
    (net (code "669") (name "unconnected-(J5-Pad35)") (class "Default")
      (node (ref "J5") (pin "35") (pinfunction "35_35") (pintype "passive"))
    )
    (net (code "670") (name "unconnected-(J5-Pad36)") (class "Default")
      (node (ref "J5") (pin "36") (pinfunction "36_36") (pintype "passive"))
    )
    (net (code "671") (name "unconnected-(J5-Pad37)") (class "Default")
      (node (ref "J5") (pin "37") (pinfunction "37_37") (pintype "passive"))
    )
    (net (code "672") (name "unconnected-(J5-Pad38)") (class "Default")
      (node (ref "J5") (pin "38") (pinfunction "38_38") (pintype "passive"))
    )
    (net (code "673") (name "unconnected-(J5-Pad39)") (class "Default")
      (node (ref "J5") (pin "39") (pinfunction "39_39") (pintype "passive"))
    )
    (net (code "674") (name "unconnected-(J5-Pad40)") (class "Default")
      (node (ref "J5") (pin "40") (pinfunction "40_40") (pintype "passive"))
    )
    (net (code "675") (name "unconnected-(J5-Pad41)") (class "Default")
      (node (ref "J5") (pin "41") (pinfunction "41_41") (pintype "passive"))
    )
    (net (code "676") (name "unconnected-(J5-Pad42)") (class "Default")
      (node (ref "J5") (pin "42") (pinfunction "42_42") (pintype "passive"))
    )
    (net (code "677") (name "unconnected-(J5-Pad43)") (class "Default")
      (node (ref "J5") (pin "43") (pinfunction "43_43") (pintype "passive"))
    )
    (net (code "678") (name "unconnected-(J5-Pad44)") (class "Default")
      (node (ref "J5") (pin "44") (pinfunction "44_44") (pintype "passive"))
    )
    (net (code "679") (name "unconnected-(J5-Pad45)") (class "Default")
      (node (ref "J5") (pin "45") (pinfunction "45_45") (pintype "passive"))
    )
    (net (code "680") (name "unconnected-(J5-Pad46)") (class "Default")
      (node (ref "J5") (pin "46") (pinfunction "46_46") (pintype "passive"))
    )
    (net (code "681") (name "unconnected-(J5-Pad47)") (class "Default")
      (node (ref "J5") (pin "47") (pinfunction "47_47") (pintype "passive"))
    )
    (net (code "682") (name "unconnected-(J5-Pad48)") (class "Default")
      (node (ref "J5") (pin "48") (pinfunction "48_48") (pintype "passive"))
    )
    (net (code "683") (name "unconnected-(J5-Pad49)") (class "Default")
      (node (ref "J5") (pin "49") (pinfunction "49_49") (pintype "passive"))
    )
    (net (code "684") (name "unconnected-(J5-Pad50)") (class "Default")
      (node (ref "J5") (pin "50") (pinfunction "50_50") (pintype "passive"))
    )
    (net (code "685") (name "unconnected-(J5-Pad51)") (class "Default")
      (node (ref "J5") (pin "51") (pinfunction "51_51") (pintype "passive"))
    )
    (net (code "686") (name "unconnected-(J5-Pad52)") (class "Default")
      (node (ref "J5") (pin "52") (pinfunction "52_52") (pintype "passive"))
    )
    (net (code "687") (name "unconnected-(J5-Pad53)") (class "Default")
      (node (ref "J5") (pin "53") (pinfunction "53_53") (pintype "passive"))
    )
    (net (code "688") (name "unconnected-(J5-Pad54)") (class "Default")
      (node (ref "J5") (pin "54") (pinfunction "54_54") (pintype "passive"))
    )
    (net (code "689") (name "unconnected-(J5-Pad55)") (class "Default")
      (node (ref "J5") (pin "55") (pinfunction "55_55") (pintype "passive"))
    )
    (net (code "690") (name "unconnected-(J5-Pad56)") (class "Default")
      (node (ref "J5") (pin "56") (pinfunction "56_56") (pintype "passive"))
    )
    (net (code "691") (name "unconnected-(J5-Pad57)") (class "Default")
      (node (ref "J5") (pin "57") (pinfunction "57_57") (pintype "passive"))
    )
    (net (code "692") (name "unconnected-(J5-Pad58)") (class "Default")
      (node (ref "J5") (pin "58") (pinfunction "58_58") (pintype "passive"))
    )
    (net (code "693") (name "unconnected-(J5-Pad59)") (class "Default")
      (node (ref "J5") (pin "59") (pinfunction "59_59") (pintype "passive"))
    )
    (net (code "694") (name "unconnected-(J5-Pad60)") (class "Default")
      (node (ref "J5") (pin "60") (pinfunction "60_60") (pintype "passive"))
    )
    (net (code "695") (name "unconnected-(J5-Pad61)") (class "Default")
      (node (ref "J5") (pin "61") (pinfunction "61_61") (pintype "passive"))
    )
    (net (code "696") (name "unconnected-(J5-Pad62)") (class "Default")
      (node (ref "J5") (pin "62") (pinfunction "62_62") (pintype "passive"))
    )
    (net (code "697") (name "unconnected-(J5-Pad63)") (class "Default")
      (node (ref "J5") (pin "63") (pinfunction "63_63") (pintype "passive"))
    )
    (net (code "698") (name "unconnected-(J5-Pad64)") (class "Default")
      (node (ref "J5") (pin "64") (pinfunction "64_64") (pintype "passive"))
    )
    (net (code "699") (name "unconnected-(J5-Pad65)") (class "Default")
      (node (ref "J5") (pin "65") (pinfunction "65_65") (pintype "passive"))
    )
    (net (code "700") (name "unconnected-(J5-Pad66)") (class "Default")
      (node (ref "J5") (pin "66") (pinfunction "66_66") (pintype "passive"))
    )
    (net (code "701") (name "unconnected-(J5-Pad67)") (class "Default")
      (node (ref "J5") (pin "67") (pinfunction "67_67") (pintype "passive"))
    )
    (net (code "702") (name "unconnected-(J5-Pad68)") (class "Default")
      (node (ref "J5") (pin "68") (pinfunction "68_68") (pintype "passive"))
    )
    (net (code "703") (name "unconnected-(J5-Pad69)") (class "Default")
      (node (ref "J5") (pin "69") (pinfunction "69_69") (pintype "passive"))
    )
    (net (code "704") (name "unconnected-(J5-Pad70)") (class "Default")
      (node (ref "J5") (pin "70") (pinfunction "70_70") (pintype "passive"))
    )
    (net (code "705") (name "unconnected-(J5-Pad71)") (class "Default")
      (node (ref "J5") (pin "71") (pinfunction "71_71") (pintype "passive"))
    )
    (net (code "706") (name "unconnected-(J5-Pad72)") (class "Default")
      (node (ref "J5") (pin "72") (pinfunction "72_72") (pintype "passive"))
    )
    (net (code "707") (name "unconnected-(J5-Pad73)") (class "Default")
      (node (ref "J5") (pin "73") (pinfunction "73_73") (pintype "passive"))
    )
    (net (code "708") (name "unconnected-(J5-Pad74)") (class "Default")
      (node (ref "J5") (pin "74") (pinfunction "74_74") (pintype "passive"))
    )
    (net (code "709") (name "unconnected-(J5-Pad75)") (class "Default")
      (node (ref "J5") (pin "75") (pinfunction "75_75") (pintype "passive"))
    )
    (net (code "710") (name "unconnected-(J5-Pad76)") (class "Default")
      (node (ref "J5") (pin "76") (pinfunction "76_76") (pintype "passive"))
    )
    (net (code "711") (name "unconnected-(J5-Pad77)") (class "Default")
      (node (ref "J5") (pin "77") (pinfunction "77_77") (pintype "passive"))
    )
    (net (code "712") (name "unconnected-(J5-Pad78)") (class "Default")
      (node (ref "J5") (pin "78") (pinfunction "78_78") (pintype "passive"))
    )
    (net (code "713") (name "unconnected-(J5-Pad79)") (class "Default")
      (node (ref "J5") (pin "79") (pinfunction "79_79") (pintype "passive"))
    )
    (net (code "714") (name "unconnected-(J5-Pad80)") (class "Default")
      (node (ref "J5") (pin "80") (pinfunction "80_80") (pintype "passive"))
    )
    (net (code "715") (name "unconnected-(J5-Pad81)") (class "Default")
      (node (ref "J5") (pin "81") (pinfunction "81_81") (pintype "passive"))
    )
    (net (code "716") (name "unconnected-(J5-Pad82)") (class "Default")
      (node (ref "J5") (pin "82") (pinfunction "82_82") (pintype "passive"))
    )
    (net (code "717") (name "unconnected-(J5-Pad83)") (class "Default")
      (node (ref "J5") (pin "83") (pinfunction "83_83") (pintype "passive"))
    )
    (net (code "718") (name "unconnected-(J5-Pad84)") (class "Default")
      (node (ref "J5") (pin "84") (pinfunction "84_84") (pintype "passive"))
    )
    (net (code "719") (name "unconnected-(J5-Pad85)") (class "Default")
      (node (ref "J5") (pin "85") (pinfunction "85_85") (pintype "passive"))
    )
    (net (code "720") (name "unconnected-(J5-Pad86)") (class "Default")
      (node (ref "J5") (pin "86") (pinfunction "86_86") (pintype "passive"))
    )
    (net (code "721") (name "unconnected-(J5-Pad87)") (class "Default")
      (node (ref "J5") (pin "87") (pinfunction "87_87") (pintype "passive"))
    )
    (net (code "722") (name "unconnected-(J5-Pad88)") (class "Default")
      (node (ref "J5") (pin "88") (pinfunction "88_88") (pintype "passive"))
    )
    (net (code "723") (name "unconnected-(J5-Pad89)") (class "Default")
      (node (ref "J5") (pin "89") (pinfunction "89_89") (pintype "passive"))
    )
    (net (code "724") (name "unconnected-(J5-Pad90)") (class "Default")
      (node (ref "J5") (pin "90") (pinfunction "90_90") (pintype "passive"))
    )
    (net (code "725") (name "unconnected-(J5-Pad91)") (class "Default")
      (node (ref "J5") (pin "91") (pinfunction "91_91") (pintype "passive"))
    )
    (net (code "726") (name "unconnected-(J5-Pad92)") (class "Default")
      (node (ref "J5") (pin "92") (pinfunction "92_92") (pintype "passive"))
    )
    (net (code "727") (name "unconnected-(J5-Pad93)") (class "Default")
      (node (ref "J5") (pin "93") (pinfunction "93_93") (pintype "passive"))
    )
    (net (code "728") (name "unconnected-(J5-Pad94)") (class "Default")
      (node (ref "J5") (pin "94") (pinfunction "94_94") (pintype "passive"))
    )
    (net (code "729") (name "unconnected-(J5-Pad95)") (class "Default")
      (node (ref "J5") (pin "95") (pinfunction "95_95") (pintype "passive"))
    )
    (net (code "730") (name "unconnected-(J5-Pad96)") (class "Default")
      (node (ref "J5") (pin "96") (pinfunction "96_96") (pintype "passive"))
    )
    (net (code "731") (name "unconnected-(J5-Pad97)") (class "Default")
      (node (ref "J5") (pin "97") (pinfunction "97_97") (pintype "passive"))
    )
    (net (code "732") (name "unconnected-(J5-Pad98)") (class "Default")
      (node (ref "J5") (pin "98") (pinfunction "98_98") (pintype "passive"))
    )
    (net (code "733") (name "unconnected-(J5-Pad99)") (class "Default")
      (node (ref "J5") (pin "99") (pinfunction "99_99") (pintype "passive"))
    )
    (net (code "734") (name "unconnected-(J5-Pad100)") (class "Default")
      (node (ref "J5") (pin "100") (pinfunction "100_100") (pintype "passive"))
    )
    (net (code "735") (name "unconnected-(J5-Pad101)") (class "Default")
      (node (ref "J5") (pin "101") (pinfunction "101_101") (pintype "passive"))
    )
    (net (code "736") (name "unconnected-(J5-Pad102)") (class "Default")
      (node (ref "J5") (pin "102") (pinfunction "102_102") (pintype "passive"))
    )
    (net (code "737") (name "unconnected-(J5-Pad103)") (class "Default")
      (node (ref "J5") (pin "103") (pinfunction "103_103") (pintype "passive"))
    )
    (net (code "738") (name "unconnected-(J5-Pad104)") (class "Default")
      (node (ref "J5") (pin "104") (pinfunction "104_104") (pintype "passive"))
    )
    (net (code "739") (name "unconnected-(J5-Pad105)") (class "Default")
      (node (ref "J5") (pin "105") (pinfunction "105_105") (pintype "passive"))
    )
    (net (code "740") (name "unconnected-(J5-Pad106)") (class "Default")
      (node (ref "J5") (pin "106") (pinfunction "106_106") (pintype "passive"))
    )
    (net (code "741") (name "unconnected-(J5-Pad107)") (class "Default")
      (node (ref "J5") (pin "107") (pinfunction "107_107") (pintype "passive"))
    )
    (net (code "742") (name "unconnected-(J5-Pad108)") (class "Default")
      (node (ref "J5") (pin "108") (pinfunction "108_108") (pintype "passive"))
    )
    (net (code "743") (name "unconnected-(J5-Pad109)") (class "Default")
      (node (ref "J5") (pin "109") (pinfunction "109_109") (pintype "passive"))
    )
    (net (code "744") (name "unconnected-(J5-Pad110)") (class "Default")
      (node (ref "J5") (pin "110") (pinfunction "110_110") (pintype "passive"))
    )
    (net (code "745") (name "unconnected-(J5-Pad111)") (class "Default")
      (node (ref "J5") (pin "111") (pinfunction "111_111") (pintype "passive"))
    )
    (net (code "746") (name "unconnected-(J5-Pad112)") (class "Default")
      (node (ref "J5") (pin "112") (pinfunction "112_112") (pintype "passive"))
    )
    (net (code "747") (name "unconnected-(J5-Pad113)") (class "Default")
      (node (ref "J5") (pin "113") (pinfunction "113_113") (pintype "passive"))
    )
    (net (code "748") (name "unconnected-(J5-Pad114)") (class "Default")
      (node (ref "J5") (pin "114") (pinfunction "114_114") (pintype "passive"))
    )
    (net (code "749") (name "unconnected-(J5-Pad115)") (class "Default")
      (node (ref "J5") (pin "115") (pinfunction "115_115") (pintype "passive"))
    )
    (net (code "750") (name "unconnected-(J5-Pad116)") (class "Default")
      (node (ref "J5") (pin "116") (pinfunction "116_116") (pintype "passive"))
    )
    (net (code "751") (name "unconnected-(J5-Pad117)") (class "Default")
      (node (ref "J5") (pin "117") (pinfunction "117_117") (pintype "passive"))
    )
    (net (code "752") (name "unconnected-(J5-Pad118)") (class "Default")
      (node (ref "J5") (pin "118") (pinfunction "118_118") (pintype "passive"))
    )
    (net (code "753") (name "unconnected-(J5-Pad119)") (class "Default")
      (node (ref "J5") (pin "119") (pinfunction "119_119") (pintype "passive"))
    )
    (net (code "754") (name "unconnected-(J5-Pad120)") (class "Default")
      (node (ref "J5") (pin "120") (pinfunction "120_120") (pintype "passive"))
    )
    (net (code "755") (name "unconnected-(J5-Pad121)") (class "Default")
      (node (ref "J5") (pin "121") (pinfunction "121_121") (pintype "passive"))
    )
    (net (code "756") (name "unconnected-(J5-Pad122)") (class "Default")
      (node (ref "J5") (pin "122") (pinfunction "122_122") (pintype "passive"))
    )
    (net (code "757") (name "unconnected-(J5-Pad123)") (class "Default")
      (node (ref "J5") (pin "123") (pinfunction "123_123") (pintype "passive"))
    )
    (net (code "758") (name "unconnected-(J5-Pad124)") (class "Default")
      (node (ref "J5") (pin "124") (pinfunction "124_124") (pintype "passive"))
    )
    (net (code "759") (name "unconnected-(J5-Pad125)") (class "Default")
      (node (ref "J5") (pin "125") (pinfunction "125_125") (pintype "passive"))
    )
    (net (code "760") (name "unconnected-(J5-Pad126)") (class "Default")
      (node (ref "J5") (pin "126") (pinfunction "126_126") (pintype "passive"))
    )
    (net (code "761") (name "unconnected-(J5-Pad127)") (class "Default")
      (node (ref "J5") (pin "127") (pinfunction "127_127") (pintype "passive"))
    )
    (net (code "762") (name "unconnected-(J5-Pad128)") (class "Default")
      (node (ref "J5") (pin "128") (pinfunction "128_128") (pintype "passive"))
    )
    (net (code "763") (name "unconnected-(J5-Pad129)") (class "Default")
      (node (ref "J5") (pin "129") (pinfunction "129_129") (pintype "passive"))
    )
    (net (code "764") (name "unconnected-(J5-Pad130)") (class "Default")
      (node (ref "J5") (pin "130") (pinfunction "130_130") (pintype "passive"))
    )
    (net (code "765") (name "unconnected-(J5-Pad131)") (class "Default")
      (node (ref "J5") (pin "131") (pinfunction "131_131") (pintype "passive"))
    )
    (net (code "766") (name "unconnected-(J5-Pad132)") (class "Default")
      (node (ref "J5") (pin "132") (pinfunction "132_132") (pintype "passive"))
    )
    (net (code "767") (name "unconnected-(J5-Pad133)") (class "Default")
      (node (ref "J5") (pin "133") (pinfunction "133_133") (pintype "passive"))
    )
    (net (code "768") (name "unconnected-(J5-Pad134)") (class "Default")
      (node (ref "J5") (pin "134") (pinfunction "134_134") (pintype "passive"))
    )
    (net (code "769") (name "unconnected-(J5-Pad135)") (class "Default")
      (node (ref "J5") (pin "135") (pinfunction "135_135") (pintype "passive"))
    )
    (net (code "770") (name "unconnected-(J5-Pad136)") (class "Default")
      (node (ref "J5") (pin "136") (pinfunction "136_136") (pintype "passive"))
    )
    (net (code "771") (name "unconnected-(J5-Pad137)") (class "Default")
      (node (ref "J5") (pin "137") (pinfunction "137_137") (pintype "passive"))
    )
    (net (code "772") (name "unconnected-(J5-Pad138)") (class "Default")
      (node (ref "J5") (pin "138") (pinfunction "138_138") (pintype "passive"))
    )
    (net (code "773") (name "unconnected-(J5-Pad139)") (class "Default")
      (node (ref "J5") (pin "139") (pinfunction "139_139") (pintype "passive"))
    )
    (net (code "774") (name "unconnected-(J5-Pad140)") (class "Default")
      (node (ref "J5") (pin "140") (pinfunction "140_140") (pintype "passive"))
    )
    (net (code "775") (name "unconnected-(J5-Pad141)") (class "Default")
      (node (ref "J5") (pin "141") (pinfunction "141_141") (pintype "passive"))
    )
    (net (code "776") (name "unconnected-(J5-Pad142)") (class "Default")
      (node (ref "J5") (pin "142") (pinfunction "142_142") (pintype "passive"))
    )
    (net (code "777") (name "unconnected-(J5-Pad143)") (class "Default")
      (node (ref "J5") (pin "143") (pinfunction "143_143") (pintype "passive"))
    )
    (net (code "778") (name "unconnected-(J5-Pad144)") (class "Default")
      (node (ref "J5") (pin "144") (pinfunction "144_144") (pintype "passive"))
    )
    (net (code "779") (name "unconnected-(J5-Pad145)") (class "Default")
      (node (ref "J5") (pin "145") (pinfunction "145_145") (pintype "passive"))
    )
    (net (code "780") (name "unconnected-(J5-Pad146)") (class "Default")
      (node (ref "J5") (pin "146") (pinfunction "146_146") (pintype "passive"))
    )
    (net (code "781") (name "unconnected-(J5-Pad147)") (class "Default")
      (node (ref "J5") (pin "147") (pinfunction "147_147") (pintype "passive"))
    )
    (net (code "782") (name "unconnected-(J5-Pad148)") (class "Default")
      (node (ref "J5") (pin "148") (pinfunction "148_148") (pintype "passive"))
    )
    (net (code "783") (name "unconnected-(J5-Pad149)") (class "Default")
      (node (ref "J5") (pin "149") (pinfunction "149_149") (pintype "passive"))
    )
    (net (code "784") (name "unconnected-(J5-Pad150)") (class "Default")
      (node (ref "J5") (pin "150") (pinfunction "150_150") (pintype "passive"))
    )
    (net (code "785") (name "unconnected-(J5-Pad151)") (class "Default")
      (node (ref "J5") (pin "151") (pinfunction "151_151") (pintype "passive"))
    )
    (net (code "786") (name "unconnected-(J5-Pad152)") (class "Default")
      (node (ref "J5") (pin "152") (pinfunction "152_152") (pintype "passive"))
    )
    (net (code "787") (name "unconnected-(J5-Pad153)") (class "Default")
      (node (ref "J5") (pin "153") (pinfunction "153_153") (pintype "passive"))
    )
    (net (code "788") (name "unconnected-(J5-Pad154)") (class "Default")
      (node (ref "J5") (pin "154") (pinfunction "154_154") (pintype "passive"))
    )
    (net (code "789") (name "unconnected-(J5-Pad155)") (class "Default")
      (node (ref "J5") (pin "155") (pinfunction "155_155") (pintype "passive"))
    )
    (net (code "790") (name "unconnected-(J5-Pad156)") (class "Default")
      (node (ref "J5") (pin "156") (pinfunction "156_156") (pintype "passive"))
    )
    (net (code "791") (name "unconnected-(J5-Pad157)") (class "Default")
      (node (ref "J5") (pin "157") (pinfunction "157_157") (pintype "passive"))
    )
    (net (code "792") (name "unconnected-(J5-Pad158)") (class "Default")
      (node (ref "J5") (pin "158") (pinfunction "158_158") (pintype "passive"))
    )
    (net (code "793") (name "unconnected-(J5-Pad159)") (class "Default")
      (node (ref "J5") (pin "159") (pinfunction "159_159") (pintype "passive"))
    )
    (net (code "794") (name "unconnected-(J5-Pad160)") (class "Default")
      (node (ref "J5") (pin "160") (pinfunction "160_160") (pintype "passive"))
    )
    (net (code "795") (name "unconnected-(J5-Pad161)") (class "Default")
      (node (ref "J5") (pin "161") (pinfunction "161_161") (pintype "passive"))
    )
    (net (code "796") (name "unconnected-(J5-Pad162)") (class "Default")
      (node (ref "J5") (pin "162") (pinfunction "162_162") (pintype "passive"))
    )
    (net (code "797") (name "unconnected-(J5-Pad163)") (class "Default")
      (node (ref "J5") (pin "163") (pinfunction "163_163") (pintype "passive"))
    )
    (net (code "798") (name "unconnected-(J5-Pad164)") (class "Default")
      (node (ref "J5") (pin "164") (pinfunction "164_164") (pintype "passive"))
    )
    (net (code "799") (name "unconnected-(J5-Pad165)") (class "Default")
      (node (ref "J5") (pin "165") (pinfunction "165_165") (pintype "passive"))
    )
    (net (code "800") (name "unconnected-(J5-Pad166)") (class "Default")
      (node (ref "J5") (pin "166") (pinfunction "166_166") (pintype "passive"))
    )
    (net (code "801") (name "unconnected-(J5-Pad167)") (class "Default")
      (node (ref "J5") (pin "167") (pinfunction "167_167") (pintype "passive"))
    )
    (net (code "802") (name "unconnected-(J5-Pad168)") (class "Default")
      (node (ref "J5") (pin "168") (pinfunction "168_168") (pintype "passive"))
    )
    (net (code "803") (name "unconnected-(J5-Pad169)") (class "Default")
      (node (ref "J5") (pin "169") (pinfunction "169_169") (pintype "passive"))
    )
    (net (code "804") (name "unconnected-(J5-Pad170)") (class "Default")
      (node (ref "J5") (pin "170") (pinfunction "170_170") (pintype "passive"))
    )
    (net (code "805") (name "unconnected-(J5-Pad171)") (class "Default")
      (node (ref "J5") (pin "171") (pinfunction "171_171") (pintype "passive"))
    )
    (net (code "806") (name "unconnected-(J5-Pad172)") (class "Default")
      (node (ref "J5") (pin "172") (pinfunction "172_172") (pintype "passive"))
    )
    (net (code "807") (name "unconnected-(J5-Pad173)") (class "Default")
      (node (ref "J5") (pin "173") (pinfunction "173_173") (pintype "passive"))
    )
    (net (code "808") (name "unconnected-(J5-Pad174)") (class "Default")
      (node (ref "J5") (pin "174") (pinfunction "174_174") (pintype "passive"))
    )
    (net (code "809") (name "unconnected-(J5-Pad175)") (class "Default")
      (node (ref "J5") (pin "175") (pinfunction "175_175") (pintype "passive"))
    )
    (net (code "810") (name "unconnected-(J5-Pad176)") (class "Default")
      (node (ref "J5") (pin "176") (pinfunction "176_176") (pintype "passive"))
    )
    (net (code "811") (name "unconnected-(J5-Pad177)") (class "Default")
      (node (ref "J5") (pin "177") (pinfunction "177_177") (pintype "passive"))
    )
    (net (code "812") (name "unconnected-(J5-Pad178)") (class "Default")
      (node (ref "J5") (pin "178") (pinfunction "178_178") (pintype "passive"))
    )
    (net (code "813") (name "unconnected-(J5-Pad179)") (class "Default")
      (node (ref "J5") (pin "179") (pinfunction "179_179") (pintype "passive"))
    )
    (net (code "814") (name "unconnected-(J5-Pad180)") (class "Default")
      (node (ref "J5") (pin "180") (pinfunction "180_180") (pintype "passive"))
    )
    (net (code "815") (name "unconnected-(J5-Pad181)") (class "Default")
      (node (ref "J5") (pin "181") (pinfunction "181_181") (pintype "passive"))
    )
    (net (code "816") (name "unconnected-(J5-Pad182)") (class "Default")
      (node (ref "J5") (pin "182") (pinfunction "182_182") (pintype "passive"))
    )
    (net (code "817") (name "unconnected-(J5-Pad183)") (class "Default")
      (node (ref "J5") (pin "183") (pinfunction "183_183") (pintype "passive"))
    )
    (net (code "818") (name "unconnected-(J5-Pad184)") (class "Default")
      (node (ref "J5") (pin "184") (pinfunction "184_184") (pintype "passive"))
    )
    (net (code "819") (name "unconnected-(J5-Pad185)") (class "Default")
      (node (ref "J5") (pin "185") (pinfunction "185_185") (pintype "passive"))
    )
    (net (code "820") (name "unconnected-(J5-Pad186)") (class "Default")
      (node (ref "J5") (pin "186") (pinfunction "186_186") (pintype "passive"))
    )
    (net (code "821") (name "unconnected-(J5-Pad187)") (class "Default")
      (node (ref "J5") (pin "187") (pinfunction "187_187") (pintype "passive"))
    )
    (net (code "822") (name "unconnected-(J5-Pad188)") (class "Default")
      (node (ref "J5") (pin "188") (pinfunction "188_188") (pintype "passive"))
    )
    (net (code "823") (name "unconnected-(J5-Pad189)") (class "Default")
      (node (ref "J5") (pin "189") (pinfunction "189_189") (pintype "passive"))
    )
    (net (code "824") (name "unconnected-(J5-Pad190)") (class "Default")
      (node (ref "J5") (pin "190") (pinfunction "190_190") (pintype "passive"))
    )
    (net (code "825") (name "unconnected-(J5-Pad191)") (class "Default")
      (node (ref "J5") (pin "191") (pinfunction "191_191") (pintype "passive"))
    )
    (net (code "826") (name "unconnected-(J5-Pad192)") (class "Default")
      (node (ref "J5") (pin "192") (pinfunction "192_192") (pintype "passive"))
    )
    (net (code "827") (name "unconnected-(J5-Pad193)") (class "Default")
      (node (ref "J5") (pin "193") (pinfunction "193_193") (pintype "passive"))
    )
    (net (code "828") (name "unconnected-(J5-Pad194)") (class "Default")
      (node (ref "J5") (pin "194") (pinfunction "194_194") (pintype "passive"))
    )
    (net (code "829") (name "unconnected-(J5-Pad195)") (class "Default")
      (node (ref "J5") (pin "195") (pinfunction "195_195") (pintype "passive"))
    )
    (net (code "830") (name "unconnected-(J5-Pad196)") (class "Default")
      (node (ref "J5") (pin "196") (pinfunction "196_196") (pintype "passive"))
    )
    (net (code "831") (name "unconnected-(J5-Pad197)") (class "Default")
      (node (ref "J5") (pin "197") (pinfunction "197_197") (pintype "passive"))
    )
    (net (code "832") (name "unconnected-(J5-Pad198)") (class "Default")
      (node (ref "J5") (pin "198") (pinfunction "198_198") (pintype "passive"))
    )
    (net (code "833") (name "unconnected-(J5-Pad199)") (class "Default")
      (node (ref "J5") (pin "199") (pinfunction "199_199") (pintype "passive"))
    )
    (net (code "834") (name "unconnected-(J5-Pad200)") (class "Default")
      (node (ref "J5") (pin "200") (pinfunction "200_200") (pintype "passive"))
    )
    (net (code "835") (name "unconnected-(J5-Pad201)") (class "Default")
      (node (ref "J5") (pin "201") (pinfunction "201_201") (pintype "passive"))
    )
    (net (code "836") (name "unconnected-(J5-Pad202)") (class "Default")
      (node (ref "J5") (pin "202") (pinfunction "202_202") (pintype "passive"))
    )
    (net (code "837") (name "unconnected-(J5-Pad203)") (class "Default")
      (node (ref "J5") (pin "203") (pinfunction "203_203") (pintype "passive"))
    )
    (net (code "838") (name "unconnected-(J5-Pad204)") (class "Default")
      (node (ref "J5") (pin "204") (pinfunction "204_204") (pintype "passive"))
    )
    (net (code "839") (name "unconnected-(J5-Pad205)") (class "Default")
      (node (ref "J5") (pin "205") (pinfunction "205_205") (pintype "passive"))
    )
    (net (code "840") (name "unconnected-(J5-Pad206)") (class "Default")
      (node (ref "J5") (pin "206") (pinfunction "206_206") (pintype "passive"))
    )
    (net (code "841") (name "unconnected-(J5-Pad207)") (class "Default")
      (node (ref "J5") (pin "207") (pinfunction "207_207") (pintype "passive"))
    )
    (net (code "842") (name "unconnected-(J5-Pad208)") (class "Default")
      (node (ref "J5") (pin "208") (pinfunction "208_208") (pintype "passive"))
    )
    (net (code "843") (name "unconnected-(J5-Pad209)") (class "Default")
      (node (ref "J5") (pin "209") (pinfunction "209_209") (pintype "passive"))
    )
    (net (code "844") (name "unconnected-(J5-Pad210)") (class "Default")
      (node (ref "J5") (pin "210") (pinfunction "210_210") (pintype "passive"))
    )
    (net (code "845") (name "unconnected-(J5-Pad211)") (class "Default")
      (node (ref "J5") (pin "211") (pinfunction "211_211") (pintype "passive"))
    )
    (net (code "846") (name "unconnected-(J5-Pad212)") (class "Default")
      (node (ref "J5") (pin "212") (pinfunction "212_212") (pintype "passive"))
    )
    (net (code "847") (name "unconnected-(J5-Pad213)") (class "Default")
      (node (ref "J5") (pin "213") (pinfunction "213_213") (pintype "passive"))
    )
    (net (code "848") (name "unconnected-(J5-Pad214)") (class "Default")
      (node (ref "J5") (pin "214") (pinfunction "214_214") (pintype "passive"))
    )
    (net (code "849") (name "unconnected-(J5-Pad215)") (class "Default")
      (node (ref "J5") (pin "215") (pinfunction "215_215") (pintype "passive"))
    )
    (net (code "850") (name "unconnected-(J5-Pad216)") (class "Default")
      (node (ref "J5") (pin "216") (pinfunction "216_216") (pintype "passive"))
    )
    (net (code "851") (name "unconnected-(J5-Pad217)") (class "Default")
      (node (ref "J5") (pin "217") (pinfunction "217_217") (pintype "passive"))
    )
    (net (code "852") (name "unconnected-(J5-Pad218)") (class "Default")
      (node (ref "J5") (pin "218") (pinfunction "218_218") (pintype "passive"))
    )
    (net (code "853") (name "unconnected-(J5-Pad219)") (class "Default")
      (node (ref "J5") (pin "219") (pinfunction "219_219") (pintype "passive"))
    )
    (net (code "854") (name "unconnected-(J5-Pad220)") (class "Default")
      (node (ref "J5") (pin "220") (pinfunction "220_220") (pintype "passive"))
    )
    (net (code "855") (name "unconnected-(J5-Pad221)") (class "Default")
      (node (ref "J5") (pin "221") (pinfunction "221_221") (pintype "passive"))
    )
    (net (code "856") (name "unconnected-(J5-Pad222)") (class "Default")
      (node (ref "J5") (pin "222") (pinfunction "222_222") (pintype "passive"))
    )
    (net (code "857") (name "unconnected-(J5-Pad223)") (class "Default")
      (node (ref "J5") (pin "223") (pinfunction "223_223") (pintype "passive"))
    )
    (net (code "858") (name "unconnected-(J5-Pad224)") (class "Default")
      (node (ref "J5") (pin "224") (pinfunction "224_224") (pintype "passive"))
    )
    (net (code "859") (name "unconnected-(J5-Pad225)") (class "Default")
      (node (ref "J5") (pin "225") (pinfunction "225_225") (pintype "passive"))
    )
    (net (code "860") (name "unconnected-(J5-Pad226)") (class "Default")
      (node (ref "J5") (pin "226") (pinfunction "226_226") (pintype "passive"))
    )
    (net (code "861") (name "unconnected-(J5-Pad227)") (class "Default")
      (node (ref "J5") (pin "227") (pinfunction "227_227") (pintype "passive"))
    )
    (net (code "862") (name "unconnected-(J5-Pad228)") (class "Default")
      (node (ref "J5") (pin "228") (pinfunction "228_228") (pintype "passive"))
    )
    (net (code "863") (name "unconnected-(J5-Pad229)") (class "Default")
      (node (ref "J5") (pin "229") (pinfunction "229_229") (pintype "passive"))
    )
    (net (code "864") (name "unconnected-(J5-Pad230)") (class "Default")
      (node (ref "J5") (pin "230") (pinfunction "230_230") (pintype "passive"))
    )
    (net (code "865") (name "unconnected-(J5-Pad231)") (class "Default")
      (node (ref "J5") (pin "231") (pinfunction "231_231") (pintype "passive"))
    )
    (net (code "866") (name "unconnected-(J5-Pad232)") (class "Default")
      (node (ref "J5") (pin "232") (pinfunction "232_232") (pintype "passive"))
    )
    (net (code "867") (name "unconnected-(J5-Pad233)") (class "Default")
      (node (ref "J5") (pin "233") (pinfunction "233_233") (pintype "passive"))
    )
    (net (code "868") (name "unconnected-(J5-Pad234)") (class "Default")
      (node (ref "J5") (pin "234") (pinfunction "234_234") (pintype "passive"))
    )
    (net (code "869") (name "unconnected-(J5-Pad235)") (class "Default")
      (node (ref "J5") (pin "235") (pinfunction "235_235") (pintype "passive"))
    )
    (net (code "870") (name "unconnected-(J5-Pad236)") (class "Default")
      (node (ref "J5") (pin "236") (pinfunction "236_236") (pintype "passive"))
    )
    (net (code "871") (name "unconnected-(J5-Pad237)") (class "Default")
      (node (ref "J5") (pin "237") (pinfunction "237_237") (pintype "passive"))
    )
    (net (code "872") (name "unconnected-(J5-Pad238)") (class "Default")
      (node (ref "J5") (pin "238") (pinfunction "238_238") (pintype "passive"))
    )
    (net (code "873") (name "unconnected-(J5-Pad239)") (class "Default")
      (node (ref "J5") (pin "239") (pinfunction "239_239") (pintype "passive"))
    )
    (net (code "874") (name "unconnected-(J5-Pad240)") (class "Default")
      (node (ref "J5") (pin "240") (pinfunction "240_240") (pintype "passive"))
    )
    (net (code "875") (name "unconnected-(J5-Pad241)") (class "Default")
      (node (ref "J5") (pin "241") (pinfunction "241_241") (pintype "passive"))
    )
    (net (code "876") (name "unconnected-(J5-Pad242)") (class "Default")
      (node (ref "J5") (pin "242") (pinfunction "242_242") (pintype "passive"))
    )
    (net (code "877") (name "unconnected-(J5-Pad243)") (class "Default")
      (node (ref "J5") (pin "243") (pinfunction "243_243") (pintype "passive"))
    )
    (net (code "878") (name "unconnected-(J5-Pad244)") (class "Default")
      (node (ref "J5") (pin "244") (pinfunction "244_244") (pintype "passive"))
    )
    (net (code "879") (name "unconnected-(J5-Pad245)") (class "Default")
      (node (ref "J5") (pin "245") (pinfunction "245_245") (pintype "passive"))
    )
    (net (code "880") (name "unconnected-(J5-Pad246)") (class "Default")
      (node (ref "J5") (pin "246") (pinfunction "246_246") (pintype "passive"))
    )
    (net (code "881") (name "unconnected-(J5-Pad247)") (class "Default")
      (node (ref "J5") (pin "247") (pinfunction "247_247") (pintype "passive"))
    )
    (net (code "882") (name "unconnected-(J5-Pad248)") (class "Default")
      (node (ref "J5") (pin "248") (pinfunction "248_248") (pintype "passive"))
    )
    (net (code "883") (name "unconnected-(J5-Pad249)") (class "Default")
      (node (ref "J5") (pin "249") (pinfunction "249_249") (pintype "passive"))
    )
    (net (code "884") (name "unconnected-(J5-Pad250)") (class "Default")
      (node (ref "J5") (pin "250") (pinfunction "250_250") (pintype "passive"))
    )
    (net (code "885") (name "unconnected-(J5-Pad251)") (class "Default")
      (node (ref "J5") (pin "251") (pinfunction "251_251") (pintype "passive"))
    )
    (net (code "886") (name "unconnected-(J5-Pad252)") (class "Default")
      (node (ref "J5") (pin "252") (pinfunction "252_252") (pintype "passive"))
    )
    (net (code "887") (name "unconnected-(J5-Pad253)") (class "Default")
      (node (ref "J5") (pin "253") (pinfunction "253_253") (pintype "passive"))
    )
    (net (code "888") (name "unconnected-(J5-Pad254)") (class "Default")
      (node (ref "J5") (pin "254") (pinfunction "254_254") (pintype "passive"))
    )
    (net (code "889") (name "unconnected-(J5-Pad255)") (class "Default")
      (node (ref "J5") (pin "255") (pinfunction "255_255") (pintype "passive"))
    )
    (net (code "890") (name "unconnected-(J5-Pad256)") (class "Default")
      (node (ref "J5") (pin "256") (pinfunction "256_256") (pintype "passive"))
    )
    (net (code "891") (name "unconnected-(J5-Pad257)") (class "Default")
      (node (ref "J5") (pin "257") (pinfunction "257_257") (pintype "passive"))
    )
    (net (code "892") (name "unconnected-(J5-Pad258)") (class "Default")
      (node (ref "J5") (pin "258") (pinfunction "258_258") (pintype "passive"))
    )
    (net (code "893") (name "unconnected-(J5-Pad259)") (class "Default")
      (node (ref "J5") (pin "259") (pinfunction "259_259") (pintype "passive"))
    )
    (net (code "894") (name "unconnected-(J5-Pad260)") (class "Default")
      (node (ref "J5") (pin "260") (pinfunction "260_260") (pintype "passive"))
    )
  )
)
